# V2_0.net
KiCad netlist of a schematic drawn in Altium Designer
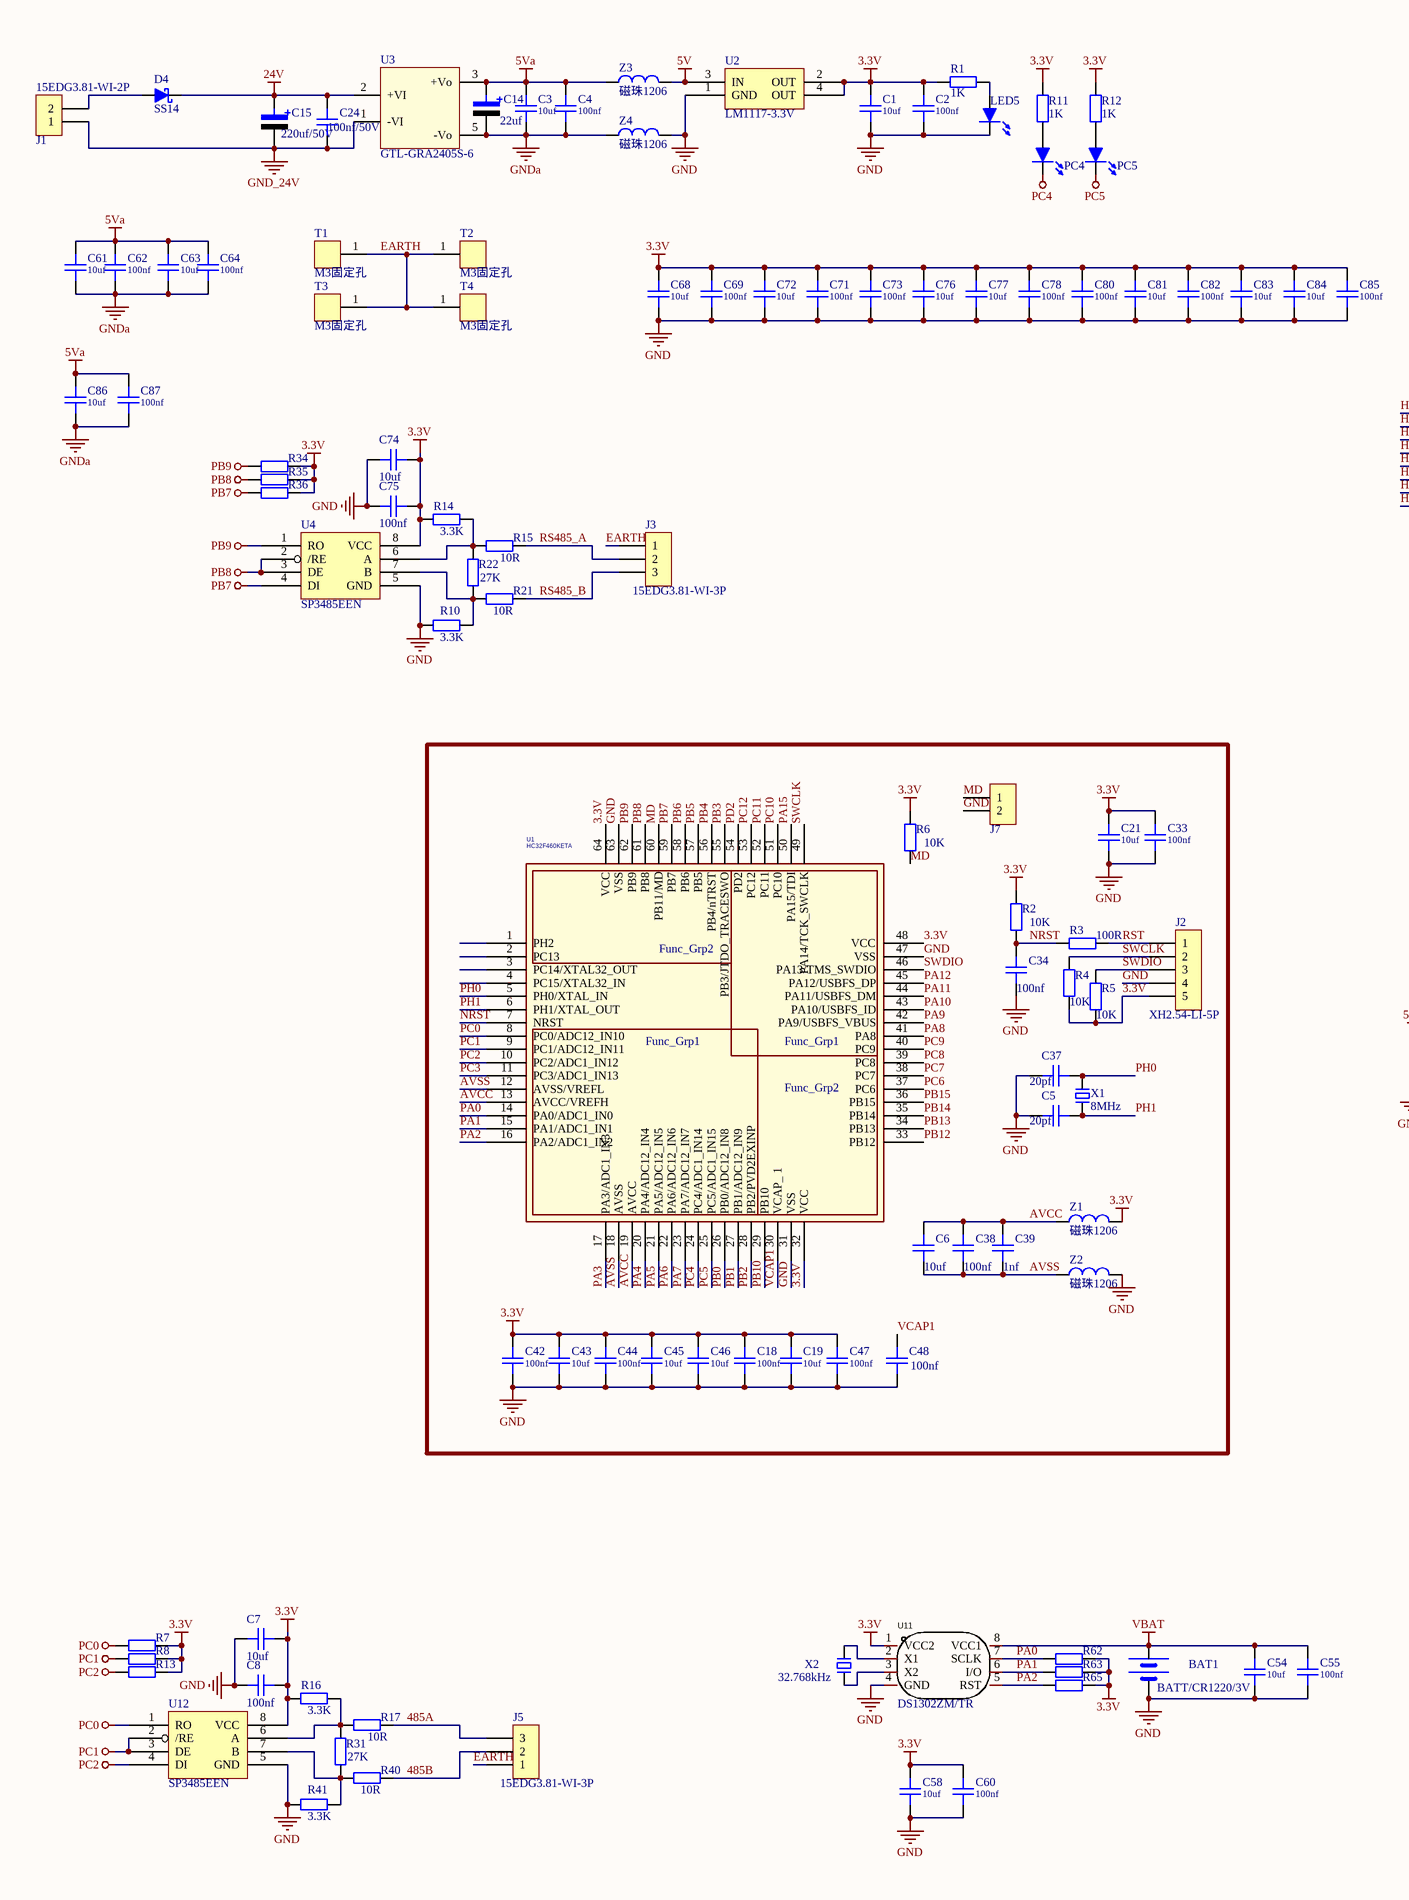
[diagram p0: 微断从V2.0.SchDoc, left]
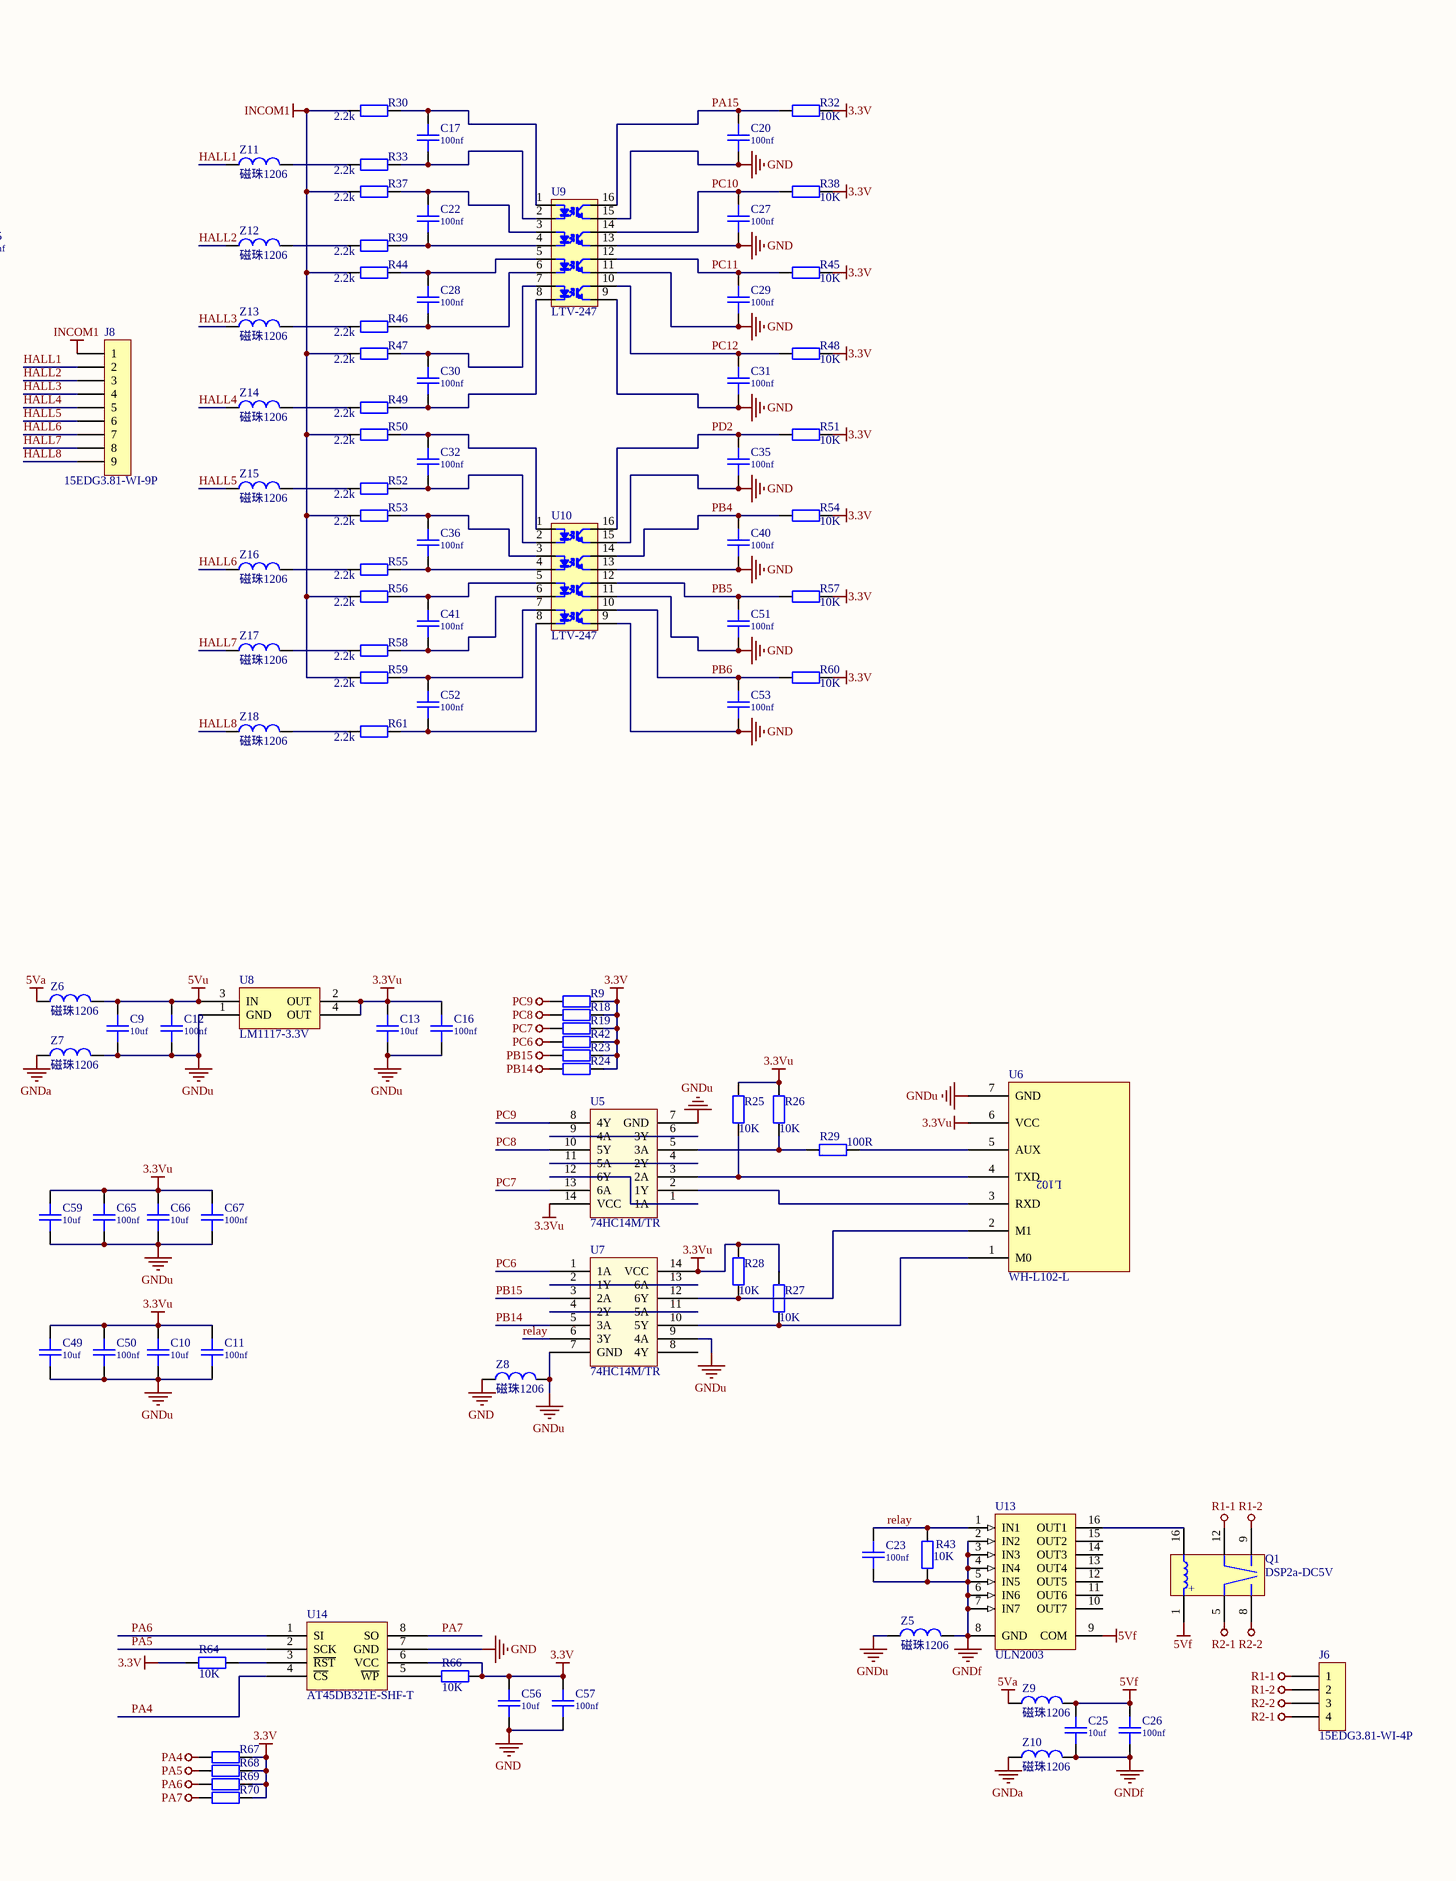
[diagram p1: 微断从V2.0.SchDoc, right]

(export (version "E")
  (design (tool "Eeschema 10.0.6"))
  (components
    (comp (ref "BAT1")
      (value "BATT/CR1220/3V")
      (footprint "CR1220_A")
      (description "CR1220/3V电池及座")
      (libsource (lib "HZConnector") (part "BAT"))
    )
    (comp (ref "C1")
      (value "10uf")
      (footprint "0805-C")
      (description "贴片瓷片电容")
      (fields (field (name "PUBLISHER") "Altium Limited"))
      (libsource (lib "jay_schlib") (part "Cap-S"))
    )
    (comp (ref "C2")
      (value "100nf")
      (footprint "0603-C")
      (description "贴片瓷片电容")
      (fields (field (name "PUBLISHER") "Altium Limited"))
      (libsource (lib "jay_schlib") (part "Cap-S"))
    )
    (comp (ref "C3")
      (value "10uf")
      (footprint "0805-C")
      (description "贴片瓷片电容")
      (fields (field (name "PUBLISHER") "Altium Limited"))
      (libsource (lib "jay_schlib") (part "Cap-S"))
    )
    (comp (ref "C4")
      (value "100nf")
      (footprint "0603-C")
      (description "贴片瓷片电容")
      (fields (field (name "PUBLISHER") "Altium Limited"))
      (libsource (lib "jay_schlib") (part "Cap-S"))
    )
    (comp (ref "C5")
      (value "20pf")
      (footprint "0603-C")
      (description "贴片瓷片电容")
      (fields (field (name "PUBLISHER") "Altium Limited"))
      (libsource (lib "jay_schlib") (part "Cap-S"))
    )
    (comp (ref "C6")
      (value "10uf")
      (footprint "0805-C")
      (description "贴片瓷片电容")
      (fields (field (name "PUBLISHER") "Altium Limited"))
      (libsource (lib "jay_schlib") (part "Cap-S"))
    )
    (comp (ref "C7")
      (value "10uf")
      (footprint "0805-C")
      (description "贴片瓷片电容")
      (fields (field (name "PUBLISHER") "Altium Limited"))
      (libsource (lib "jay_schlib") (part "Cap-S"))
    )
    (comp (ref "C8")
      (value "100nf")
      (footprint "0603-C")
      (description "贴片瓷片电容")
      (fields (field (name "PUBLISHER") "Altium Limited"))
      (libsource (lib "jay_schlib") (part "Cap-S"))
    )
    (comp (ref "C9")
      (value "10uf")
      (footprint "0805-C")
      (description "贴片瓷片电容")
      (fields (field (name "PUBLISHER") "Altium Limited"))
      (libsource (lib "jay_schlib") (part "Cap-S"))
    )
    (comp (ref "C10")
      (value "10uf")
      (footprint "0805-C")
      (description "贴片瓷片电容")
      (fields (field (name "PUBLISHER") "Altium Limited"))
      (libsource (lib "jay_schlib") (part "Cap-S"))
    )
    (comp (ref "C11")
      (value "100nf")
      (footprint "0603-C")
      (description "贴片瓷片电容")
      (fields (field (name "PUBLISHER") "Altium Limited"))
      (libsource (lib "jay_schlib") (part "Cap-S"))
    )
    (comp (ref "C12")
      (value "100nf")
      (footprint "0603-C")
      (description "贴片瓷片电容")
      (fields (field (name "PUBLISHER") "Altium Limited"))
      (libsource (lib "jay_schlib") (part "Cap-S"))
    )
    (comp (ref "C13")
      (value "10uf")
      (footprint "0805-C")
      (description "贴片瓷片电容")
      (fields (field (name "PUBLISHER") "Altium Limited"))
      (libsource (lib "jay_schlib") (part "Cap-S"))
    )
    (comp (ref "C14")
      (value "22uf")
      (footprint "CD B(3528)")
      (description "插件电解电容")
      (fields (field (name "PUBLISHER") "Altium Limited"))
      (libsource (lib "jay_schlib") (part "Cap-Pol-ER"))
    )
    (comp (ref "C15")
      (value "220uf/50V")
      (footprint "CAP 3.5*8*11.5 - BK")
      (description "插件电解电容")
      (fields (field (name "PUBLISHER") "Altium Limited"))
      (libsource (lib "jay_schlib") (part "Cap-Pol-ER"))
    )
    (comp (ref "C16")
      (value "100nf")
      (footprint "0603-C")
      (description "贴片瓷片电容")
      (fields (field (name "PUBLISHER") "Altium Limited"))
      (libsource (lib "jay_schlib") (part "Cap-S"))
    )
    (comp (ref "C17")
      (value "100nf")
      (footprint "0603-C")
      (description "贴片瓷片电容")
      (fields (field (name "PUBLISHER") "Altium Limited"))
      (libsource (lib "jay_schlib") (part "Cap-S"))
    )
    (comp (ref "C18")
      (value "100nf")
      (footprint "0603-C")
      (description "贴片瓷片电容")
      (fields (field (name "PUBLISHER") "Altium Limited"))
      (libsource (lib "jay_schlib") (part "Cap-S"))
    )
    (comp (ref "C19")
      (value "10uf")
      (footprint "0805-C")
      (description "贴片瓷片电容")
      (fields (field (name "PUBLISHER") "Altium Limited"))
      (libsource (lib "jay_schlib") (part "Cap-S"))
    )
    (comp (ref "C20")
      (value "100nf")
      (footprint "0603-C")
      (description "贴片瓷片电容")
      (fields (field (name "PUBLISHER") "Altium Limited"))
      (libsource (lib "jay_schlib") (part "Cap-S"))
    )
    (comp (ref "C21")
      (value "10uf")
      (footprint "0805-C")
      (description "贴片瓷片电容")
      (fields (field (name "PUBLISHER") "Altium Limited"))
      (libsource (lib "jay_schlib") (part "Cap-S"))
    )
    (comp (ref "C22")
      (value "100nf")
      (footprint "0603-C")
      (description "贴片瓷片电容")
      (fields (field (name "PUBLISHER") "Altium Limited"))
      (libsource (lib "jay_schlib") (part "Cap-S"))
    )
    (comp (ref "C23")
      (value "100nf")
      (footprint "0603-C")
      (description "贴片瓷片电容")
      (fields (field (name "PUBLISHER") "Altium Limited"))
      (libsource (lib "jay_schlib") (part "Cap-S"))
    )
    (comp (ref "C24")
      (value "100nf/50V")
      (footprint "0603-C")
      (description "贴片瓷片电容")
      (fields (field (name "PUBLISHER") "Altium Limited"))
      (libsource (lib "jay_schlib") (part "Cap-S"))
    )
    (comp (ref "C25")
      (value "10uf")
      (footprint "0805-C")
      (description "贴片瓷片电容")
      (fields (field (name "PUBLISHER") "Altium Limited"))
      (libsource (lib "jay_schlib") (part "Cap-S"))
    )
    (comp (ref "C26")
      (value "100nf")
      (footprint "0603-C")
      (description "贴片瓷片电容")
      (fields (field (name "PUBLISHER") "Altium Limited"))
      (libsource (lib "jay_schlib") (part "Cap-S"))
    )
    (comp (ref "C27")
      (value "100nf")
      (footprint "0603-C")
      (description "贴片瓷片电容")
      (fields (field (name "PUBLISHER") "Altium Limited"))
      (libsource (lib "jay_schlib") (part "Cap-S"))
    )
    (comp (ref "C28")
      (value "100nf")
      (footprint "0603-C")
      (description "贴片瓷片电容")
      (fields (field (name "PUBLISHER") "Altium Limited"))
      (libsource (lib "jay_schlib") (part "Cap-S"))
    )
    (comp (ref "C29")
      (value "100nf")
      (footprint "0603-C")
      (description "贴片瓷片电容")
      (fields (field (name "PUBLISHER") "Altium Limited"))
      (libsource (lib "jay_schlib") (part "Cap-S"))
    )
    (comp (ref "C30")
      (value "100nf")
      (footprint "0603-C")
      (description "贴片瓷片电容")
      (fields (field (name "PUBLISHER") "Altium Limited"))
      (libsource (lib "jay_schlib") (part "Cap-S"))
    )
    (comp (ref "C31")
      (value "100nf")
      (footprint "0603-C")
      (description "贴片瓷片电容")
      (fields (field (name "PUBLISHER") "Altium Limited"))
      (libsource (lib "jay_schlib") (part "Cap-S"))
    )
    (comp (ref "C32")
      (value "100nf")
      (footprint "0603-C")
      (description "贴片瓷片电容")
      (fields (field (name "PUBLISHER") "Altium Limited"))
      (libsource (lib "jay_schlib") (part "Cap-S"))
    )
    (comp (ref "C33")
      (value "100nf")
      (footprint "0603-C")
      (description "贴片瓷片电容")
      (fields (field (name "PUBLISHER") "Altium Limited"))
      (libsource (lib "jay_schlib") (part "Cap-S"))
    )
    (comp (ref "C34")
      (value "100nf")
      (footprint "0603-C")
      (description "贴片瓷片电容")
      (fields (field (name "PUBLISHER") "Altium Limited"))
      (libsource (lib "jay_schlib") (part "Cap-S"))
    )
    (comp (ref "C35")
      (value "100nf")
      (footprint "0603-C")
      (description "贴片瓷片电容")
      (fields (field (name "PUBLISHER") "Altium Limited"))
      (libsource (lib "jay_schlib") (part "Cap-S"))
    )
    (comp (ref "C36")
      (value "100nf")
      (footprint "0603-C")
      (description "贴片瓷片电容")
      (fields (field (name "PUBLISHER") "Altium Limited"))
      (libsource (lib "jay_schlib") (part "Cap-S"))
    )
    (comp (ref "C37")
      (value "20pf")
      (footprint "0603-C")
      (description "贴片瓷片电容")
      (fields (field (name "PUBLISHER") "Altium Limited"))
      (libsource (lib "jay_schlib") (part "Cap-S"))
    )
    (comp (ref "C38")
      (value "100nf")
      (footprint "0603-C")
      (description "贴片瓷片电容")
      (fields (field (name "PUBLISHER") "Altium Limited"))
      (libsource (lib "jay_schlib") (part "Cap-S"))
    )
    (comp (ref "C39")
      (value "1nf")
      (footprint "0603-C")
      (description "贴片瓷片电容")
      (fields (field (name "PUBLISHER") "Altium Limited"))
      (libsource (lib "jay_schlib") (part "Cap-S"))
    )
    (comp (ref "C40")
      (value "100nf")
      (footprint "0603-C")
      (description "贴片瓷片电容")
      (fields (field (name "PUBLISHER") "Altium Limited"))
      (libsource (lib "jay_schlib") (part "Cap-S"))
    )
    (comp (ref "C41")
      (value "100nf")
      (footprint "0603-C")
      (description "贴片瓷片电容")
      (fields (field (name "PUBLISHER") "Altium Limited"))
      (libsource (lib "jay_schlib") (part "Cap-S"))
    )
    (comp (ref "C42")
      (value "100nf")
      (footprint "0603-C")
      (description "贴片瓷片电容")
      (fields (field (name "PUBLISHER") "Altium Limited"))
      (libsource (lib "jay_schlib") (part "Cap-S"))
    )
    (comp (ref "C43")
      (value "10uf")
      (footprint "0805-C")
      (description "贴片瓷片电容")
      (fields (field (name "PUBLISHER") "Altium Limited"))
      (libsource (lib "jay_schlib") (part "Cap-S"))
    )
    (comp (ref "C44")
      (value "100nf")
      (footprint "0603-C")
      (description "贴片瓷片电容")
      (fields (field (name "PUBLISHER") "Altium Limited"))
      (libsource (lib "jay_schlib") (part "Cap-S"))
    )
    (comp (ref "C45")
      (value "10uf")
      (footprint "0805-C")
      (description "贴片瓷片电容")
      (fields (field (name "PUBLISHER") "Altium Limited"))
      (libsource (lib "jay_schlib") (part "Cap-S"))
    )
    (comp (ref "C46")
      (value "10uf")
      (footprint "0805-C")
      (description "贴片瓷片电容")
      (fields (field (name "PUBLISHER") "Altium Limited"))
      (libsource (lib "jay_schlib") (part "Cap-S"))
    )
    (comp (ref "C47")
      (value "100nf")
      (footprint "0603-C")
      (description "贴片瓷片电容")
      (fields (field (name "PUBLISHER") "Altium Limited"))
      (libsource (lib "jay_schlib") (part "Cap-S"))
    )
    (comp (ref "C48")
      (value "100nf")
      (footprint "0603-C")
      (description "贴片瓷片电容")
      (fields (field (name "PUBLISHER") "Altium Limited"))
      (libsource (lib "jay_schlib") (part "Cap-S"))
    )
    (comp (ref "C49")
      (value "10uf")
      (footprint "0805-C")
      (description "贴片瓷片电容")
      (fields (field (name "PUBLISHER") "Altium Limited"))
      (libsource (lib "jay_schlib") (part "Cap-S"))
    )
    (comp (ref "C50")
      (value "100nf")
      (footprint "0603-C")
      (description "贴片瓷片电容")
      (fields (field (name "PUBLISHER") "Altium Limited"))
      (libsource (lib "jay_schlib") (part "Cap-S"))
    )
    (comp (ref "C51")
      (value "100nf")
      (footprint "0603-C")
      (description "贴片瓷片电容")
      (fields (field (name "PUBLISHER") "Altium Limited"))
      (libsource (lib "jay_schlib") (part "Cap-S"))
    )
    (comp (ref "C52")
      (value "100nf")
      (footprint "0603-C")
      (description "贴片瓷片电容")
      (fields (field (name "PUBLISHER") "Altium Limited"))
      (libsource (lib "jay_schlib") (part "Cap-S"))
    )
    (comp (ref "C53")
      (value "100nf")
      (footprint "0603-C")
      (description "贴片瓷片电容")
      (fields (field (name "PUBLISHER") "Altium Limited"))
      (libsource (lib "jay_schlib") (part "Cap-S"))
    )
    (comp (ref "C54")
      (value "10uf")
      (footprint "0805-C")
      (description "贴片瓷片电容")
      (fields (field (name "PUBLISHER") "Altium Limited"))
      (libsource (lib "jay_schlib") (part "Cap-S"))
    )
    (comp (ref "C55")
      (value "100nf")
      (footprint "0603-C")
      (description "贴片瓷片电容")
      (fields (field (name "PUBLISHER") "Altium Limited"))
      (libsource (lib "jay_schlib") (part "Cap-S"))
    )
    (comp (ref "C56")
      (value "10uf")
      (footprint "0805-C")
      (description "贴片瓷片电容")
      (fields (field (name "PUBLISHER") "Altium Limited"))
      (libsource (lib "jay_schlib") (part "Cap-S"))
    )
    (comp (ref "C57")
      (value "100nf")
      (footprint "0603-C")
      (description "贴片瓷片电容")
      (fields (field (name "PUBLISHER") "Altium Limited"))
      (libsource (lib "jay_schlib") (part "Cap-S"))
    )
    (comp (ref "C58")
      (value "10uf")
      (footprint "0805-C")
      (description "贴片瓷片电容")
      (fields (field (name "PUBLISHER") "Altium Limited"))
      (libsource (lib "jay_schlib") (part "Cap-S"))
    )
    (comp (ref "C59")
      (value "10uf")
      (footprint "0805-C")
      (description "贴片瓷片电容")
      (fields (field (name "PUBLISHER") "Altium Limited"))
      (libsource (lib "jay_schlib") (part "Cap-S"))
    )
    (comp (ref "C60")
      (value "100nf")
      (footprint "0603-C")
      (description "贴片瓷片电容")
      (fields (field (name "PUBLISHER") "Altium Limited"))
      (libsource (lib "jay_schlib") (part "Cap-S"))
    )
    (comp (ref "C61")
      (value "10uf")
      (footprint "0805-C")
      (description "贴片瓷片电容")
      (fields (field (name "PUBLISHER") "Altium Limited"))
      (libsource (lib "jay_schlib") (part "Cap-S"))
    )
    (comp (ref "C62")
      (value "100nf")
      (footprint "0603-C")
      (description "贴片瓷片电容")
      (fields (field (name "PUBLISHER") "Altium Limited"))
      (libsource (lib "jay_schlib") (part "Cap-S"))
    )
    (comp (ref "C63")
      (value "10uf")
      (footprint "0805-C")
      (description "贴片瓷片电容")
      (fields (field (name "PUBLISHER") "Altium Limited"))
      (libsource (lib "jay_schlib") (part "Cap-S"))
    )
    (comp (ref "C64")
      (value "100nf")
      (footprint "0603-C")
      (description "贴片瓷片电容")
      (fields (field (name "PUBLISHER") "Altium Limited"))
      (libsource (lib "jay_schlib") (part "Cap-S"))
    )
    (comp (ref "C65")
      (value "100nf")
      (footprint "0603-C")
      (description "贴片瓷片电容")
      (fields (field (name "PUBLISHER") "Altium Limited"))
      (libsource (lib "jay_schlib") (part "Cap-S"))
    )
    (comp (ref "C66")
      (value "10uf")
      (footprint "0805-C")
      (description "贴片瓷片电容")
      (fields (field (name "PUBLISHER") "Altium Limited"))
      (libsource (lib "jay_schlib") (part "Cap-S"))
    )
    (comp (ref "C67")
      (value "100nf")
      (footprint "0603-C")
      (description "贴片瓷片电容")
      (fields (field (name "PUBLISHER") "Altium Limited"))
      (libsource (lib "jay_schlib") (part "Cap-S"))
    )
    (comp (ref "C68")
      (value "10uf")
      (footprint "0805-C")
      (description "贴片瓷片电容")
      (fields (field (name "PUBLISHER") "Altium Limited"))
      (libsource (lib "jay_schlib") (part "Cap-S"))
    )
    (comp (ref "C69")
      (value "100nf")
      (footprint "0603-C")
      (description "贴片瓷片电容")
      (fields (field (name "PUBLISHER") "Altium Limited"))
      (libsource (lib "jay_schlib") (part "Cap-S"))
    )
    (comp (ref "C71")
      (value "100nf")
      (footprint "0603-C")
      (description "贴片瓷片电容")
      (fields (field (name "PUBLISHER") "Altium Limited"))
      (libsource (lib "jay_schlib") (part "Cap-S"))
    )
    (comp (ref "C72")
      (value "10uf")
      (footprint "0805-C")
      (description "贴片瓷片电容")
      (fields (field (name "PUBLISHER") "Altium Limited"))
      (libsource (lib "jay_schlib") (part "Cap-S"))
    )
    (comp (ref "C73")
      (value "100nf")
      (footprint "0603-C")
      (description "贴片瓷片电容")
      (fields (field (name "PUBLISHER") "Altium Limited"))
      (libsource (lib "jay_schlib") (part "Cap-S"))
    )
    (comp (ref "C74")
      (value "10uf")
      (footprint "0805-C")
      (description "贴片瓷片电容")
      (fields (field (name "PUBLISHER") "Altium Limited"))
      (libsource (lib "jay_schlib") (part "Cap-S"))
    )
    (comp (ref "C75")
      (value "100nf")
      (footprint "0603-C")
      (description "贴片瓷片电容")
      (fields (field (name "PUBLISHER") "Altium Limited"))
      (libsource (lib "jay_schlib") (part "Cap-S"))
    )
    (comp (ref "C76")
      (value "10uf")
      (footprint "0805-C")
      (description "贴片瓷片电容")
      (fields (field (name "PUBLISHER") "Altium Limited"))
      (libsource (lib "jay_schlib") (part "Cap-S"))
    )
    (comp (ref "C77")
      (value "10uf")
      (footprint "0805-C")
      (description "贴片瓷片电容")
      (fields (field (name "PUBLISHER") "Altium Limited"))
      (libsource (lib "jay_schlib") (part "Cap-S"))
    )
    (comp (ref "C78")
      (value "100nf")
      (footprint "0603-C")
      (description "贴片瓷片电容")
      (fields (field (name "PUBLISHER") "Altium Limited"))
      (libsource (lib "jay_schlib") (part "Cap-S"))
    )
    (comp (ref "C80")
      (value "100nf")
      (footprint "0603-C")
      (description "贴片瓷片电容")
      (fields (field (name "PUBLISHER") "Altium Limited"))
      (libsource (lib "jay_schlib") (part "Cap-S"))
    )
    (comp (ref "C81")
      (value "10uf")
      (footprint "0805-C")
      (description "贴片瓷片电容")
      (fields (field (name "PUBLISHER") "Altium Limited"))
      (libsource (lib "jay_schlib") (part "Cap-S"))
    )
    (comp (ref "C82")
      (value "100nf")
      (footprint "0603-C")
      (description "贴片瓷片电容")
      (fields (field (name "PUBLISHER") "Altium Limited"))
      (libsource (lib "jay_schlib") (part "Cap-S"))
    )
    (comp (ref "C83")
      (value "10uf")
      (footprint "0805-C")
      (description "贴片瓷片电容")
      (fields (field (name "PUBLISHER") "Altium Limited"))
      (libsource (lib "jay_schlib") (part "Cap-S"))
    )
    (comp (ref "C84")
      (value "10uf")
      (footprint "0805-C")
      (description "贴片瓷片电容")
      (fields (field (name "PUBLISHER") "Altium Limited"))
      (libsource (lib "jay_schlib") (part "Cap-S"))
    )
    (comp (ref "C85")
      (value "100nf")
      (footprint "0603-C")
      (description "贴片瓷片电容")
      (fields (field (name "PUBLISHER") "Altium Limited"))
      (libsource (lib "jay_schlib") (part "Cap-S"))
    )
    (comp (ref "C86")
      (value "10uf")
      (footprint "0805-C")
      (description "贴片瓷片电容")
      (fields (field (name "PUBLISHER") "Altium Limited"))
      (libsource (lib "jay_schlib") (part "Cap-S"))
    )
    (comp (ref "C87")
      (value "100nf")
      (footprint "0603-C")
      (description "贴片瓷片电容")
      (fields (field (name "PUBLISHER") "Altium Limited"))
      (libsource (lib "jay_schlib") (part "Cap-S"))
    )
    (comp (ref "D4")
      (value "SS14")
      (footprint "SMA/DO-214AC")
      (description "肖特基二极管")
      (fields (field (name "PUBLISHER") "Altium Limited"))
      (libsource (lib "jay_schlib") (part "Diode2"))
    )
    (comp (ref "J1")
      (value "15EDG3.81-WI-2P")
      (footprint "15EDG3.81-WI-2P")
      (description "接插件")
      (fields (field (name "PUBLISHER") "Altium Limited"))
      (libsource (lib "jay_schlib") (part "Header 2"))
    )
    (comp (ref "J2")
      (value "XH2.54-LI-5P")
      (footprint "XH2.54-LI-5P")
      (description "接插件")
      (fields (field (name "PUBLISHER") "Altium Limited"))
      (libsource (lib "jay_schlib") (part "Header 5"))
    )
    (comp (ref "J3")
      (value "15EDG3.81-WI-3P")
      (footprint "15EDG3.81-WI-3P")
      (description "接插件")
      (fields (field (name "PUBLISHER") "Altium Limited"))
      (libsource (lib "jay_schlib") (part "Header 3"))
    )
    (comp (ref "J5")
      (value "15EDG3.81-WI-3P")
      (footprint "15EDG3.81-WI-3P")
      (description "接插件")
      (fields (field (name "PUBLISHER") "Altium Limited"))
      (libsource (lib "") (part "Header 3_1"))
    )
    (comp (ref "J6")
      (value "15EDG3.81-WI-4P")
      (footprint "15EDG3.81-WI-4P")
      (description "接插件")
      (fields (field (name "PUBLISHER") "Altium Limited"))
      (libsource (lib "jay_schlib") (part "Header 4"))
    )
    (comp (ref "J7")
      (value "排针1*2P")
      (footprint "HDR2X1_A")
      (description "接插件")
      (fields (field (name "PUBLISHER") "Altium Limited"))
      (libsource (lib "") (part "Header 2_1"))
    )
    (comp (ref "J8")
      (value "15EDG3.81-WI-9P")
      (footprint "15EDG3.81-WI-9P")
      (description "Header, 9-Pin")
      (fields (field (name "PUBLISHER") "Altium Limited"))
      (libsource (lib "jay_schlib") (part "Header 9"))
    )
    (comp (ref "LED5")
      (value "LED0603,黄绿")
      (footprint "0603-LED-G")
      (description "发光二极管")
      (fields (field (name "PUBLISHER") "Altium Limited"))
      (libsource (lib "jay_schlib") (part "LED"))
    )
    (comp (ref "PC4")
      (value "LED0603,黄绿")
      (footprint "0603-LED-G")
      (description "发光二极管")
      (fields (field (name "PUBLISHER") "Altium Limited"))
      (libsource (lib "jay_schlib") (part "LED"))
    )
    (comp (ref "PC5")
      (value "LED0603,黄绿")
      (footprint "0603-LED-G")
      (description "发光二极管")
      (fields (field (name "PUBLISHER") "Altium Limited"))
      (libsource (lib "jay_schlib") (part "LED"))
    )
    (comp (ref "Q1")
      (value "DSP2a-DC5V")
      (footprint "DSP2a-DC5V")
      (description "松下继电器")
      (libsource (lib "jay_schlib") (part "DSP2a-DC5V"))
    )
    (comp (ref "R1")
      (value "1K")
      (footprint "0603-R")
      (description "贴片电阻")
      (fields (field (name "PUBLISHER") "Altium Limited"))
      (libsource (lib "jay_schlib") (part "Res1"))
    )
    (comp (ref "R2")
      (value "10K")
      (footprint "0603-R")
      (description "贴片电阻")
      (fields (field (name "PUBLISHER") "Altium Limited"))
      (libsource (lib "") (part "Res1_2"))
    )
    (comp (ref "R3")
      (value "100R")
      (footprint "0603-R")
      (description "贴片电阻")
      (fields (field (name "PUBLISHER") "Altium Limited"))
      (libsource (lib "jay_schlib") (part "Res1"))
    )
    (comp (ref "R4")
      (value "10K")
      (footprint "0603-R")
      (description "贴片电阻")
      (fields (field (name "PUBLISHER") "Altium Limited"))
      (libsource (lib "") (part "Res1_2"))
    )
    (comp (ref "R5")
      (value "10K")
      (footprint "0603-R")
      (description "贴片电阻")
      (fields (field (name "PUBLISHER") "Altium Limited"))
      (libsource (lib "") (part "Res1_2"))
    )
    (comp (ref "R6")
      (value "10K")
      (footprint "0603-R")
      (description "贴片电阻")
      (fields (field (name "PUBLISHER") "Altium Limited"))
      (libsource (lib "") (part "Res1_2"))
    )
    (comp (ref "R7")
      (value "10K")
      (footprint "0603-R")
      (description "贴片电阻")
      (fields (field (name "PUBLISHER") "Altium Limited"))
      (libsource (lib "") (part "Res1_1"))
    )
    (comp (ref "R8")
      (value "10K")
      (footprint "0603-R")
      (description "贴片电阻")
      (fields (field (name "PUBLISHER") "Altium Limited"))
      (libsource (lib "") (part "Res1_1"))
    )
    (comp (ref "R9")
      (value "10K")
      (footprint "0603-R")
      (description "贴片电阻")
      (fields (field (name "PUBLISHER") "Altium Limited"))
      (libsource (lib "jay_schlib") (part "Res1"))
    )
    (comp (ref "R10")
      (value "3.3K")
      (footprint "0603-R")
      (description "Resistor")
      (fields (field (name "PUBLISHER") "Altium Limited"))
      (libsource (lib "*") (part "Res2"))
    )
    (comp (ref "R11")
      (value "1K")
      (footprint "0603-R")
      (description "贴片电阻")
      (fields (field (name "PUBLISHER") "Altium Limited"))
      (libsource (lib "") (part "Res1_2"))
    )
    (comp (ref "R12")
      (value "1K")
      (footprint "0603-R")
      (description "贴片电阻")
      (fields (field (name "PUBLISHER") "Altium Limited"))
      (libsource (lib "") (part "Res1_2"))
    )
    (comp (ref "R13")
      (value "10K")
      (footprint "0603-R")
      (description "贴片电阻")
      (fields (field (name "PUBLISHER") "Altium Limited"))
      (libsource (lib "") (part "Res1_1"))
    )
    (comp (ref "R14")
      (value "3.3K")
      (footprint "0603-R")
      (description "Resistor")
      (fields (field (name "PUBLISHER") "Altium Limited"))
      (libsource (lib "") (part "Res2_2"))
    )
    (comp (ref "R15")
      (value "10R")
      (footprint "0603-R")
      (description "Resistor")
      (fields (field (name "PUBLISHER") "Altium Limited"))
      (libsource (lib "*") (part "Res2"))
    )
    (comp (ref "R16")
      (value "3.3K")
      (footprint "0603-R")
      (description "Resistor")
      (fields (field (name "PUBLISHER") "Altium Limited"))
      (libsource (lib "") (part "Res2_2"))
    )
    (comp (ref "R17")
      (value "10R")
      (footprint "0603-R")
      (description "Resistor")
      (fields (field (name "PUBLISHER") "Altium Limited"))
      (libsource (lib "*") (part "Res2"))
    )
    (comp (ref "R18")
      (value "10K")
      (footprint "0603-R")
      (description "贴片电阻")
      (fields (field (name "PUBLISHER") "Altium Limited"))
      (libsource (lib "jay_schlib") (part "Res1"))
    )
    (comp (ref "R19")
      (value "10K")
      (footprint "0603-R")
      (description "贴片电阻")
      (fields (field (name "PUBLISHER") "Altium Limited"))
      (libsource (lib "jay_schlib") (part "Res1"))
    )
    (comp (ref "R21")
      (value "10R")
      (footprint "0603-R")
      (description "Resistor")
      (fields (field (name "PUBLISHER") "Altium Limited"))
      (libsource (lib "*") (part "Res2"))
    )
    (comp (ref "R22")
      (value "27K")
      (footprint "0603-R")
      (description "Resistor")
      (fields (field (name "PUBLISHER") "Altium Limited"))
      (libsource (lib "") (part "Res2_1"))
    )
    (comp (ref "R23")
      (value "10K")
      (footprint "0603-R")
      (description "贴片电阻")
      (fields (field (name "PUBLISHER") "Altium Limited"))
      (libsource (lib "jay_schlib") (part "Res1"))
    )
    (comp (ref "R24")
      (value "10K")
      (footprint "0603-R")
      (description "贴片电阻")
      (fields (field (name "PUBLISHER") "Altium Limited"))
      (libsource (lib "jay_schlib") (part "Res1"))
    )
    (comp (ref "R25")
      (value "10K")
      (footprint "0603-R")
      (description "贴片电阻")
      (fields (field (name "PUBLISHER") "Altium Limited"))
      (libsource (lib "") (part "Res1_2"))
    )
    (comp (ref "R26")
      (value "10K")
      (footprint "0603-R")
      (description "贴片电阻")
      (fields (field (name "PUBLISHER") "Altium Limited"))
      (libsource (lib "") (part "Res1_2"))
    )
    (comp (ref "R27")
      (value "10K")
      (footprint "0603-R")
      (description "贴片电阻")
      (fields (field (name "PUBLISHER") "Altium Limited"))
      (libsource (lib "") (part "Res1_2"))
    )
    (comp (ref "R28")
      (value "10K")
      (footprint "0603-R")
      (description "贴片电阻")
      (fields (field (name "PUBLISHER") "Altium Limited"))
      (libsource (lib "") (part "Res1_2"))
    )
    (comp (ref "R29")
      (value "100R")
      (footprint "0603-R")
      (description "贴片电阻")
      (fields (field (name "PUBLISHER") "Altium Limited"))
      (libsource (lib "jay_schlib") (part "Res1"))
    )
    (comp (ref "R30")
      (value "2.2k")
      (footprint "0603-R")
      (description "贴片电阻")
      (fields (field (name "PUBLISHER") "Altium Limited"))
      (libsource (lib "jay_schlib") (part "Res1"))
    )
    (comp (ref "R31")
      (value "27K")
      (footprint "0603-R")
      (description "Resistor")
      (fields (field (name "PUBLISHER") "Altium Limited"))
      (libsource (lib "") (part "Res2_1"))
    )
    (comp (ref "R32")
      (value "10K")
      (footprint "0603-R")
      (description "贴片电阻")
      (fields (field (name "PUBLISHER") "Altium Limited"))
      (libsource (lib "jay_schlib") (part "Res1"))
    )
    (comp (ref "R33")
      (value "2.2k")
      (footprint "0603-R")
      (description "贴片电阻")
      (fields (field (name "PUBLISHER") "Altium Limited"))
      (libsource (lib "jay_schlib") (part "Res1"))
    )
    (comp (ref "R34")
      (value "10K")
      (footprint "0603-R")
      (description "贴片电阻")
      (fields (field (name "PUBLISHER") "Altium Limited"))
      (libsource (lib "") (part "Res1_1"))
    )
    (comp (ref "R35")
      (value "10K")
      (footprint "0603-R")
      (description "贴片电阻")
      (fields (field (name "PUBLISHER") "Altium Limited"))
      (libsource (lib "") (part "Res1_1"))
    )
    (comp (ref "R36")
      (value "10K")
      (footprint "0603-R")
      (description "贴片电阻")
      (fields (field (name "PUBLISHER") "Altium Limited"))
      (libsource (lib "") (part "Res1_1"))
    )
    (comp (ref "R37")
      (value "2.2k")
      (footprint "0603-R")
      (description "贴片电阻")
      (fields (field (name "PUBLISHER") "Altium Limited"))
      (libsource (lib "jay_schlib") (part "Res1"))
    )
    (comp (ref "R38")
      (value "10K")
      (footprint "0603-R")
      (description "贴片电阻")
      (fields (field (name "PUBLISHER") "Altium Limited"))
      (libsource (lib "jay_schlib") (part "Res1"))
    )
    (comp (ref "R39")
      (value "2.2k")
      (footprint "0603-R")
      (description "贴片电阻")
      (fields (field (name "PUBLISHER") "Altium Limited"))
      (libsource (lib "jay_schlib") (part "Res1"))
    )
    (comp (ref "R40")
      (value "10R")
      (footprint "0603-R")
      (description "Resistor")
      (fields (field (name "PUBLISHER") "Altium Limited"))
      (libsource (lib "*") (part "Res2"))
    )
    (comp (ref "R41")
      (value "3.3K")
      (footprint "0603-R")
      (description "Resistor")
      (fields (field (name "PUBLISHER") "Altium Limited"))
      (libsource (lib "*") (part "Res2"))
    )
    (comp (ref "R42")
      (value "10K")
      (footprint "0603-R")
      (description "贴片电阻")
      (fields (field (name "PUBLISHER") "Altium Limited"))
      (libsource (lib "jay_schlib") (part "Res1"))
    )
    (comp (ref "R43")
      (value "10K")
      (footprint "0603-R")
      (description "贴片电阻")
      (fields (field (name "PUBLISHER") "Altium Limited"))
      (libsource (lib "") (part "Res1_1"))
    )
    (comp (ref "R44")
      (value "2.2k")
      (footprint "0603-R")
      (description "贴片电阻")
      (fields (field (name "PUBLISHER") "Altium Limited"))
      (libsource (lib "jay_schlib") (part "Res1"))
    )
    (comp (ref "R45")
      (value "10K")
      (footprint "0603-R")
      (description "贴片电阻")
      (fields (field (name "PUBLISHER") "Altium Limited"))
      (libsource (lib "jay_schlib") (part "Res1"))
    )
    (comp (ref "R46")
      (value "2.2k")
      (footprint "0603-R")
      (description "贴片电阻")
      (fields (field (name "PUBLISHER") "Altium Limited"))
      (libsource (lib "jay_schlib") (part "Res1"))
    )
    (comp (ref "R47")
      (value "2.2k")
      (footprint "0603-R")
      (description "贴片电阻")
      (fields (field (name "PUBLISHER") "Altium Limited"))
      (libsource (lib "jay_schlib") (part "Res1"))
    )
    (comp (ref "R48")
      (value "10K")
      (footprint "0603-R")
      (description "贴片电阻")
      (fields (field (name "PUBLISHER") "Altium Limited"))
      (libsource (lib "jay_schlib") (part "Res1"))
    )
    (comp (ref "R49")
      (value "2.2k")
      (footprint "0603-R")
      (description "贴片电阻")
      (fields (field (name "PUBLISHER") "Altium Limited"))
      (libsource (lib "jay_schlib") (part "Res1"))
    )
    (comp (ref "R50")
      (value "2.2k")
      (footprint "0603-R")
      (description "贴片电阻")
      (fields (field (name "PUBLISHER") "Altium Limited"))
      (libsource (lib "jay_schlib") (part "Res1"))
    )
    (comp (ref "R51")
      (value "10K")
      (footprint "0603-R")
      (description "贴片电阻")
      (fields (field (name "PUBLISHER") "Altium Limited"))
      (libsource (lib "jay_schlib") (part "Res1"))
    )
    (comp (ref "R52")
      (value "2.2k")
      (footprint "0603-R")
      (description "贴片电阻")
      (fields (field (name "PUBLISHER") "Altium Limited"))
      (libsource (lib "jay_schlib") (part "Res1"))
    )
    (comp (ref "R53")
      (value "2.2k")
      (footprint "0603-R")
      (description "贴片电阻")
      (fields (field (name "PUBLISHER") "Altium Limited"))
      (libsource (lib "jay_schlib") (part "Res1"))
    )
    (comp (ref "R54")
      (value "10K")
      (footprint "0603-R")
      (description "贴片电阻")
      (fields (field (name "PUBLISHER") "Altium Limited"))
      (libsource (lib "jay_schlib") (part "Res1"))
    )
    (comp (ref "R55")
      (value "2.2k")
      (footprint "0603-R")
      (description "贴片电阻")
      (fields (field (name "PUBLISHER") "Altium Limited"))
      (libsource (lib "jay_schlib") (part "Res1"))
    )
    (comp (ref "R56")
      (value "2.2k")
      (footprint "0603-R")
      (description "贴片电阻")
      (fields (field (name "PUBLISHER") "Altium Limited"))
      (libsource (lib "jay_schlib") (part "Res1"))
    )
    (comp (ref "R57")
      (value "10K")
      (footprint "0603-R")
      (description "贴片电阻")
      (fields (field (name "PUBLISHER") "Altium Limited"))
      (libsource (lib "jay_schlib") (part "Res1"))
    )
    (comp (ref "R58")
      (value "2.2k")
      (footprint "0603-R")
      (description "贴片电阻")
      (fields (field (name "PUBLISHER") "Altium Limited"))
      (libsource (lib "jay_schlib") (part "Res1"))
    )
    (comp (ref "R59")
      (value "2.2k")
      (footprint "0603-R")
      (description "贴片电阻")
      (fields (field (name "PUBLISHER") "Altium Limited"))
      (libsource (lib "jay_schlib") (part "Res1"))
    )
    (comp (ref "R60")
      (value "10K")
      (footprint "0603-R")
      (description "贴片电阻")
      (fields (field (name "PUBLISHER") "Altium Limited"))
      (libsource (lib "jay_schlib") (part "Res1"))
    )
    (comp (ref "R61")
      (value "2.2k")
      (footprint "0603-R")
      (description "贴片电阻")
      (fields (field (name "PUBLISHER") "Altium Limited"))
      (libsource (lib "jay_schlib") (part "Res1"))
    )
    (comp (ref "R62")
      (value "10K")
      (footprint "0603-R")
      (description "贴片电阻")
      (fields (field (name "PUBLISHER") "Altium Limited"))
      (libsource (lib "jay_schlib") (part "Res1"))
    )
    (comp (ref "R63")
      (value "10K")
      (footprint "0603-R")
      (description "贴片电阻")
      (fields (field (name "PUBLISHER") "Altium Limited"))
      (libsource (lib "jay_schlib") (part "Res1"))
    )
    (comp (ref "R64")
      (value "10K")
      (footprint "0603-R")
      (description "贴片电阻")
      (fields (field (name "PUBLISHER") "Altium Limited"))
      (libsource (lib "jay_schlib") (part "Res1"))
    )
    (comp (ref "R65")
      (value "10K")
      (footprint "0603-R")
      (description "贴片电阻")
      (fields (field (name "PUBLISHER") "Altium Limited"))
      (libsource (lib "jay_schlib") (part "Res1"))
    )
    (comp (ref "R66")
      (value "10K")
      (footprint "0603-R")
      (description "贴片电阻")
      (fields (field (name "PUBLISHER") "Altium Limited"))
      (libsource (lib "jay_schlib") (part "Res1"))
    )
    (comp (ref "R67")
      (value "10K")
      (footprint "0603-R")
      (description "贴片电阻")
      (fields (field (name "PUBLISHER") "Altium Limited"))
      (libsource (lib "") (part "Res1_1"))
    )
    (comp (ref "R68")
      (value "10K")
      (footprint "0603-R")
      (description "贴片电阻")
      (fields (field (name "PUBLISHER") "Altium Limited"))
      (libsource (lib "") (part "Res1_1"))
    )
    (comp (ref "R69")
      (value "10K")
      (footprint "0603-R")
      (description "贴片电阻")
      (fields (field (name "PUBLISHER") "Altium Limited"))
      (libsource (lib "") (part "Res1_1"))
    )
    (comp (ref "R70")
      (value "10K")
      (footprint "0603-R")
      (description "贴片电阻")
      (fields (field (name "PUBLISHER") "Altium Limited"))
      (libsource (lib "") (part "Res1_1"))
    )
    (comp (ref "T1")
      (value "M3固定孔")
      (footprint "M3_N")
      (description "自选封装")
      (libsource (lib "jay_schlib") (part "something_1"))
    )
    (comp (ref "T2")
      (value "M3固定孔")
      (footprint "M3_N")
      (description "自选封装")
      (libsource (lib "") (part "something_1_1"))
    )
    (comp (ref "T3")
      (value "M3固定孔")
      (footprint "M3_N")
      (description "自选封装")
      (libsource (lib "jay_schlib") (part "something_1"))
    )
    (comp (ref "T4")
      (value "M3固定孔")
      (footprint "M3_N")
      (description "自选封装")
      (libsource (lib "") (part "something_1_1"))
    )
    (comp (ref "U1")
      (value "HC32F460KETA")
      (footprint "LQFP-64")
      (libsource (lib "HC32F460") (part "HC32F460KETA"))
    )
    (comp (ref "U2")
      (value "LM1117-3.3V")
      (footprint "SOT223")
      (description "3.3V稳压芯片")
      (libsource (lib "jay_schlib") (part "AMS1117"))
    )
    (comp (ref "U3")
      (value "GTL-GRA2405S-6")
      (footprint "GTL-GRA")
      (description "冠图电子电源模块")
      (libsource (lib "jay_schlib") (part "GTL-GRA"))
    )
    (comp (ref "U4") (value "SP3485EEN") (footprint "SOIC-8") (libsource (lib "*") (part "MAX3082")))
    (comp (ref "U5")
      (value "74HC14M/TR")
      (footprint "SOIC-14")
      (description "反相器")
      (libsource (lib "jay_schlib") (part "74HC14"))
    )
    (comp (ref "U6")
      (value "WH-L102-L")
      (footprint "WH-L102-L_Lib_V1.0")
      (libsource (lib "WH-L102-L_Lib_V1.0") (part "WH-L102-L"))
    )
    (comp (ref "U7")
      (value "74HC14M/TR")
      (footprint "SOIC-14")
      (description "反相器")
      (libsource (lib "") (part "74HC14_1"))
    )
    (comp (ref "U8")
      (value "LM1117-3.3V")
      (footprint "SOT223")
      (description "3.3V稳压芯片")
      (libsource (lib "jay_schlib") (part "AMS1117"))
    )
    (comp (ref "U9")
      (value "LTV-247")
      (footprint "SOIC-16-9.1mm")
      (description "光耦")
      (fields (field (name "PUBLISHER") "Altium Limited"))
      (libsource (lib "jay_schlib") (part "LTV-247"))
    )
    (comp (ref "U10")
      (value "LTV-247")
      (footprint "SOIC-16-9.1mm")
      (description "光耦")
      (fields (field (name "PUBLISHER") "Altium Limited"))
      (libsource (lib "jay_schlib") (part "LTV-247"))
    )
    (comp (ref "U11")
      (value "DS1302ZM/TR")
      (footprint "SOIC-8")
      (fields (field (name "MANUFACTURER") "HGSEMI(华冠)"))
      (libsource (lib "altium-import") (part "root_0_DS1302ZM/TR_"))
    )
    (comp (ref "U12") (value "SP3485EEN") (footprint "SOIC-8") (libsource (lib "*") (part "MAX3082")))
    (comp (ref "U13") (value "ULN2003") (footprint "SOIC-16") (libsource (lib "jay_schlib") (part "ULN2003")))
    (comp (ref "U14")
      (value "AT45DB321E-SHF-T")
      (footprint "SOIC-8-208mil")
      (libsource (lib "*") (part "AT45DB642D"))
    )
    (comp (ref "X1")
      (value "8MHz")
      (footprint "OSC HC-49SMD")
      (description "2脚无源脚晶振")
      (fields (field (name "版权归属") "源创客"))
      (libsource (lib "10.1 - 保险丝-晶振") (part "XTAL-2P"))
    )
    (comp (ref "X2")
      (value "32.768kHz")
      (footprint "OSC HC-49SMD")
      (description "2脚无源脚晶振")
      (fields (field (name "版权归属") "源创客"))
      (libsource (lib "10.1 - 保险丝-晶振") (part "XTAL-2P"))
    )
    (comp (ref "Z1")
      (value "磁珠1206")
      (footprint "1206-R-RP")
      (description "电感")
      (fields (field (name "Comment") "磁珠1206/SCBG321609U600T") (field (name "PUBLISHER") "Altium Limited"))
      (libsource (lib "jay_schlib") (part "Inductor"))
    )
    (comp (ref "Z2")
      (value "磁珠1206")
      (footprint "1206-R-RP")
      (description "电感")
      (fields (field (name "Comment") "磁珠1206/SCBG321609U600T") (field (name "PUBLISHER") "Altium Limited"))
      (libsource (lib "jay_schlib") (part "Inductor"))
    )
    (comp (ref "Z3")
      (value "磁珠1206")
      (footprint "1206-R-RP")
      (description "电感")
      (fields (field (name "Comment") "磁珠1206/SCBG321609U600T") (field (name "PUBLISHER") "Altium Limited"))
      (libsource (lib "jay_schlib") (part "Inductor"))
    )
    (comp (ref "Z4")
      (value "磁珠1206")
      (footprint "1206-R-RP")
      (description "电感")
      (fields (field (name "Comment") "磁珠1206/SCBG321609U600T") (field (name "PUBLISHER") "Altium Limited"))
      (libsource (lib "jay_schlib") (part "Inductor"))
    )
    (comp (ref "Z5")
      (value "磁珠1206")
      (footprint "1206-R-RP")
      (description "电感")
      (fields (field (name "Comment") "磁珠1206/SCBG321609U600T") (field (name "PUBLISHER") "Altium Limited"))
      (libsource (lib "jay_schlib") (part "Inductor"))
    )
    (comp (ref "Z6")
      (value "磁珠1206")
      (footprint "1206-R-RP")
      (description "电感")
      (fields (field (name "Comment") "磁珠1206/SCBG321609U600T") (field (name "PUBLISHER") "Altium Limited"))
      (libsource (lib "jay_schlib") (part "Inductor"))
    )
    (comp (ref "Z7")
      (value "磁珠1206")
      (footprint "1206-R-RP")
      (description "电感")
      (fields (field (name "Comment") "磁珠1206/SCBG321609U600T") (field (name "PUBLISHER") "Altium Limited"))
      (libsource (lib "jay_schlib") (part "Inductor"))
    )
    (comp (ref "Z8")
      (value "磁珠1206")
      (footprint "1206-R-RP")
      (description "电感")
      (fields (field (name "Comment") "磁珠1206/SCBG321609U600T") (field (name "PUBLISHER") "Altium Limited"))
      (libsource (lib "jay_schlib") (part "Inductor"))
    )
    (comp (ref "Z9")
      (value "磁珠1206")
      (footprint "1206-R-RP")
      (description "电感")
      (fields (field (name "Comment") "磁珠1206/SCBG321609U600T") (field (name "PUBLISHER") "Altium Limited"))
      (libsource (lib "jay_schlib") (part "Inductor"))
    )
    (comp (ref "Z10")
      (value "磁珠1206")
      (footprint "1206-R-RP")
      (description "电感")
      (fields (field (name "Comment") "磁珠1206/SCBG321609U600T") (field (name "PUBLISHER") "Altium Limited"))
      (libsource (lib "jay_schlib") (part "Inductor"))
    )
    (comp (ref "Z11")
      (value "磁珠1206")
      (footprint "1206-R-RP")
      (description "电感")
      (fields (field (name "Comment") "磁珠1206/SCBG321609U600T") (field (name "PUBLISHER") "Altium Limited"))
      (libsource (lib "jay_schlib") (part "Inductor"))
    )
    (comp (ref "Z12")
      (value "磁珠1206")
      (footprint "1206-R-RP")
      (description "电感")
      (fields (field (name "Comment") "磁珠1206/SCBG321609U600T") (field (name "PUBLISHER") "Altium Limited"))
      (libsource (lib "jay_schlib") (part "Inductor"))
    )
    (comp (ref "Z13")
      (value "磁珠1206")
      (footprint "1206-R-RP")
      (description "电感")
      (fields (field (name "Comment") "磁珠1206/SCBG321609U600T") (field (name "PUBLISHER") "Altium Limited"))
      (libsource (lib "jay_schlib") (part "Inductor"))
    )
    (comp (ref "Z14")
      (value "磁珠1206")
      (footprint "1206-R-RP")
      (description "电感")
      (fields (field (name "Comment") "磁珠1206/SCBG321609U600T") (field (name "PUBLISHER") "Altium Limited"))
      (libsource (lib "jay_schlib") (part "Inductor"))
    )
    (comp (ref "Z15")
      (value "磁珠1206")
      (footprint "1206-R-RP")
      (description "电感")
      (fields (field (name "Comment") "磁珠1206/SCBG321609U600T") (field (name "PUBLISHER") "Altium Limited"))
      (libsource (lib "jay_schlib") (part "Inductor"))
    )
    (comp (ref "Z16")
      (value "磁珠1206")
      (footprint "1206-R-RP")
      (description "电感")
      (fields (field (name "Comment") "磁珠1206/SCBG321609U600T") (field (name "PUBLISHER") "Altium Limited"))
      (libsource (lib "jay_schlib") (part "Inductor"))
    )
    (comp (ref "Z17")
      (value "磁珠1206")
      (footprint "1206-R-RP")
      (description "电感")
      (fields (field (name "Comment") "磁珠1206/SCBG321609U600T") (field (name "PUBLISHER") "Altium Limited"))
      (libsource (lib "jay_schlib") (part "Inductor"))
    )
    (comp (ref "Z18")
      (value "磁珠1206")
      (footprint "1206-R-RP")
      (description "电感")
      (fields (field (name "Comment") "磁珠1206/SCBG321609U600T") (field (name "PUBLISHER") "Altium Limited"))
      (libsource (lib "jay_schlib") (part "Inductor"))
    )
  )
  (nets
    (net (code "1") (name "/485A") (class "Default")
      (node (ref "J5") (pin "3") (pinfunction "3_3") (pintype "passive"))
      (node (ref "R17") (pin "1") (pinfunction "1_1") (pintype "passive"))
    )
    (net (code "2") (name "/485B") (class "Default")
      (node (ref "J5") (pin "2") (pinfunction "2_2") (pintype "passive"))
      (node (ref "R40") (pin "1") (pinfunction "1_1") (pintype "passive"))
    )
    (net (code "3") (name "/AVCC") (class "Default")
      (node (ref "C38") (pin "1") (pinfunction "1_1") (pintype "passive"))
      (node (ref "C39") (pin "1") (pinfunction "1_1") (pintype "passive"))
      (node (ref "C6") (pin "1") (pinfunction "1_1") (pintype "passive"))
      (node (ref "U1") (pin "13") (pinfunction "AVCC/VREFH_13") (pintype "power_in"))
      (node (ref "U1") (pin "19") (pinfunction "AVCC_19") (pintype "power_in"))
      (node (ref "Z1") (pin "1") (pinfunction "1_1") (pintype "passive"))
    )
    (net (code "4") (name "/AVSS") (class "Default")
      (node (ref "C38") (pin "2") (pinfunction "2_2") (pintype "passive"))
      (node (ref "C39") (pin "2") (pinfunction "2_2") (pintype "passive"))
      (node (ref "C6") (pin "2") (pinfunction "2_2") (pintype "passive"))
      (node (ref "U1") (pin "12") (pinfunction "AVSS/VREFL_12") (pintype "power_in"))
      (node (ref "U1") (pin "18") (pinfunction "AVSS_18") (pintype "power_in"))
      (node (ref "Z2") (pin "1") (pinfunction "1_1") (pintype "passive"))
    )
    (net (code "5") (name "/EARTH") (class "Default")
      (node (ref "J3") (pin "1") (pinfunction "1_1") (pintype "passive"))
      (node (ref "J5") (pin "1") (pinfunction "1_1") (pintype "passive"))
      (node (ref "T1") (pin "1") (pinfunction "PG_1") (pintype "passive"))
      (node (ref "T2") (pin "1") (pinfunction "PG_1") (pintype "passive"))
      (node (ref "T3") (pin "1") (pinfunction "PG_1") (pintype "passive"))
      (node (ref "T4") (pin "1") (pinfunction "PG_1") (pintype "passive"))
    )
    (net (code "6") (name "/HALL1") (class "Default")
      (node (ref "J8") (pin "2") (pinfunction "2_2") (pintype "passive"))
      (node (ref "Z11") (pin "1") (pinfunction "1_1") (pintype "passive"))
    )
    (net (code "7") (name "/HALL2") (class "Default")
      (node (ref "J8") (pin "3") (pinfunction "3_3") (pintype "passive"))
      (node (ref "Z12") (pin "1") (pinfunction "1_1") (pintype "passive"))
    )
    (net (code "8") (name "/HALL3") (class "Default")
      (node (ref "J8") (pin "4") (pinfunction "4_4") (pintype "passive"))
      (node (ref "Z13") (pin "1") (pinfunction "1_1") (pintype "passive"))
    )
    (net (code "9") (name "/HALL4") (class "Default")
      (node (ref "J8") (pin "5") (pinfunction "5_5") (pintype "passive"))
      (node (ref "Z14") (pin "1") (pinfunction "1_1") (pintype "passive"))
    )
    (net (code "10") (name "/HALL5") (class "Default")
      (node (ref "J8") (pin "6") (pinfunction "6_6") (pintype "passive"))
      (node (ref "Z15") (pin "1") (pinfunction "1_1") (pintype "passive"))
    )
    (net (code "11") (name "/HALL6") (class "Default")
      (node (ref "J8") (pin "7") (pinfunction "7_7") (pintype "passive"))
      (node (ref "Z16") (pin "1") (pinfunction "1_1") (pintype "passive"))
    )
    (net (code "12") (name "/HALL7") (class "Default")
      (node (ref "J8") (pin "8") (pinfunction "8_8") (pintype "passive"))
      (node (ref "Z17") (pin "1") (pinfunction "1_1") (pintype "passive"))
    )
    (net (code "13") (name "/HALL8") (class "Default")
      (node (ref "J8") (pin "9") (pinfunction "9_9") (pintype "passive"))
      (node (ref "Z18") (pin "1") (pinfunction "1_1") (pintype "passive"))
    )
    (net (code "14") (name "/MD") (class "Default")
      (node (ref "J7") (pin "1") (pinfunction "1_1") (pintype "passive"))
      (node (ref "R6") (pin "1") (pinfunction "1_1") (pintype "passive"))
      (node (ref "U1") (pin "60") (pinfunction "PB11/MD_60") (pintype "passive"))
    )
    (net (code "15") (name "/NRST") (class "Default")
      (node (ref "C34") (pin "1") (pinfunction "1_1") (pintype "passive"))
      (node (ref "R2") (pin "1") (pinfunction "1_1") (pintype "passive"))
      (node (ref "R3") (pin "2") (pinfunction "2_2") (pintype "passive"))
      (node (ref "U1") (pin "7") (pinfunction "NRST_7") (pintype "passive"))
    )
    (net (code "16") (name "/PA0") (class "Default")
      (node (ref "R62") (pin "2") (pinfunction "2_2") (pintype "passive"))
      (node (ref "U1") (pin "14") (pinfunction "PA0/ADC1_IN0_14") (pintype "passive"))
      (node (ref "U11") (pin "7") (pinfunction "SCLK_7") (pintype "passive"))
    )
    (net (code "17") (name "/PA1") (class "Default")
      (node (ref "R63") (pin "2") (pinfunction "2_2") (pintype "passive"))
      (node (ref "U1") (pin "15") (pinfunction "PA1/ADC1_IN1_15") (pintype "passive"))
      (node (ref "U11") (pin "6") (pinfunction "I/O_6") (pintype "passive"))
    )
    (net (code "18") (name "/PA2") (class "Default")
      (node (ref "R65") (pin "2") (pinfunction "2_2") (pintype "passive"))
      (node (ref "U1") (pin "16") (pinfunction "PA2/ADC1_IN2_16") (pintype "passive"))
      (node (ref "U11") (pin "5") (pinfunction "RST_5") (pintype "passive"))
    )
    (net (code "19") (name "/PA3") (class "Default")
      (node (ref "U1") (pin "17") (pinfunction "PA3/ADC1_IN3_17") (pintype "passive"))
    )
    (net (code "20") (name "/PA8") (class "Default")
      (node (ref "U1") (pin "41") (pinfunction "PA8_41") (pintype "passive"))
    )
    (net (code "21") (name "/PA9") (class "Default")
      (node (ref "U1") (pin "42") (pinfunction "PA9/USBFS_VBUS_42") (pintype "passive"))
    )
    (net (code "22") (name "/PA10") (class "Default")
      (node (ref "U1") (pin "43") (pinfunction "PA10/USBFS_ID_43") (pintype "passive"))
    )
    (net (code "23") (name "/PA11") (class "Default")
      (node (ref "U1") (pin "44") (pinfunction "PA11/USBFS_DM_44") (pintype "passive"))
    )
    (net (code "24") (name "/PA12") (class "Default")
      (node (ref "U1") (pin "45") (pinfunction "PA12/USBFS_DP_45") (pintype "passive"))
    )
    (net (code "25") (name "/PA15") (class "Default")
      (node (ref "C20") (pin "2") (pinfunction "2_2") (pintype "passive"))
      (node (ref "R32") (pin "2") (pinfunction "2_2") (pintype "passive"))
      (node (ref "U1") (pin "50") (pinfunction "PA15/TDI_50") (pintype "passive"))
      (node (ref "U9") (pin "16") (pinfunction "OUT_16") (pintype "passive"))
    )
    (net (code "26") (name "/PB0") (class "Default")
      (node (ref "U1") (pin "26") (pinfunction "PB0/ADC12_IN8_26") (pintype "passive"))
    )
    (net (code "27") (name "/PB1") (class "Default")
      (node (ref "U1") (pin "27") (pinfunction "PB1/ADC12_IN9_27") (pintype "passive"))
    )
    (net (code "28") (name "/PB2") (class "Default")
      (node (ref "U1") (pin "28") (pinfunction "PB2/PVD2EXINP_28") (pintype "passive"))
    )
    (net (code "29") (name "/PB3") (class "Default")
      (node (ref "U1") (pin "55") (pinfunction "PB3/JTDO_TRACESWO_55") (pintype "passive"))
    )
    (net (code "30") (name "/PB4") (class "Default")
      (node (ref "C40") (pin "2") (pinfunction "2_2") (pintype "passive"))
      (node (ref "R54") (pin "2") (pinfunction "2_2") (pintype "passive"))
      (node (ref "U1") (pin "56") (pinfunction "PB4/nTRST_56") (pintype "passive"))
      (node (ref "U10") (pin "14") (pinfunction "OUT_14") (pintype "passive"))
    )
    (net (code "31") (name "/PB5") (class "Default")
      (node (ref "C51") (pin "2") (pinfunction "2_2") (pintype "passive"))
      (node (ref "R57") (pin "2") (pinfunction "2_2") (pintype "passive"))
      (node (ref "U1") (pin "57") (pinfunction "PB5_57") (pintype "passive"))
      (node (ref "U10") (pin "12") (pinfunction "OUT_12") (pintype "passive"))
    )
    (net (code "32") (name "/PB6") (class "Default")
      (node (ref "C53") (pin "2") (pinfunction "2_2") (pintype "passive"))
      (node (ref "R60") (pin "2") (pinfunction "2_2") (pintype "passive"))
      (node (ref "U1") (pin "58") (pinfunction "PB6_58") (pintype "passive"))
      (node (ref "U10") (pin "10") (pinfunction "OUT_10") (pintype "passive"))
    )
    (net (code "33") (name "/PB10") (class "Default")
      (node (ref "U1") (pin "29") (pinfunction "PB10_29") (pintype "passive"))
    )
    (net (code "34") (name "/PB12") (class "Default")
      (node (ref "U1") (pin "33") (pinfunction "PB12_33") (pintype "passive"))
    )
    (net (code "35") (name "/PB13") (class "Default")
      (node (ref "U1") (pin "34") (pinfunction "PB13_34") (pintype "passive"))
    )
    (net (code "36") (name "/PC3") (class "Default")
      (node (ref "U1") (pin "11") (pinfunction "PC3/ADC1_IN13_11") (pintype "passive"))
    )
    (net (code "37") (name "/PC10") (class "Default")
      (node (ref "C27") (pin "2") (pinfunction "2_2") (pintype "passive"))
      (node (ref "R38") (pin "2") (pinfunction "2_2") (pintype "passive"))
      (node (ref "U1") (pin "51") (pinfunction "PC10_51") (pintype "passive"))
      (node (ref "U9") (pin "14") (pinfunction "OUT_14") (pintype "passive"))
    )
    (net (code "38") (name "/PC11") (class "Default")
      (node (ref "C29") (pin "2") (pinfunction "2_2") (pintype "passive"))
      (node (ref "R45") (pin "2") (pinfunction "2_2") (pintype "passive"))
      (node (ref "U1") (pin "52") (pinfunction "PC11_52") (pintype "passive"))
      (node (ref "U9") (pin "12") (pinfunction "OUT_12") (pintype "passive"))
    )
    (net (code "39") (name "/PC12") (class "Default")
      (node (ref "C31") (pin "2") (pinfunction "2_2") (pintype "passive"))
      (node (ref "R48") (pin "2") (pinfunction "2_2") (pintype "passive"))
      (node (ref "U1") (pin "53") (pinfunction "PC12_53") (pintype "passive"))
      (node (ref "U9") (pin "10") (pinfunction "OUT_10") (pintype "passive"))
    )
    (net (code "40") (name "/PD2") (class "Default")
      (node (ref "C35") (pin "2") (pinfunction "2_2") (pintype "passive"))
      (node (ref "R51") (pin "2") (pinfunction "2_2") (pintype "passive"))
      (node (ref "U1") (pin "54") (pinfunction "PD2_54") (pintype "passive"))
      (node (ref "U10") (pin "16") (pinfunction "OUT_16") (pintype "passive"))
    )
    (net (code "41") (name "/PH0") (class "Default")
      (node (ref "C37") (pin "2") (pinfunction "2_2") (pintype "passive"))
      (node (ref "U1") (pin "5") (pinfunction "PH0/XTAL_IN_5") (pintype "passive"))
      (node (ref "X1") (pin "2") (pinfunction "2_2") (pintype "passive"))
    )
    (net (code "42") (name "/PH1") (class "Default")
      (node (ref "C5") (pin "2") (pinfunction "2_2") (pintype "passive"))
      (node (ref "U1") (pin "6") (pinfunction "PH1/XTAL_OUT_6") (pintype "passive"))
      (node (ref "X1") (pin "1") (pinfunction "1_1") (pintype "passive"))
    )
    (net (code "43") (name "/RS485_A") (class "Default")
      (node (ref "J3") (pin "2") (pinfunction "2_2") (pintype "passive"))
      (node (ref "R15") (pin "1") (pinfunction "1_1") (pintype "passive"))
    )
    (net (code "44") (name "/RS485_B") (class "Default")
      (node (ref "J3") (pin "3") (pinfunction "3_3") (pintype "passive"))
      (node (ref "R21") (pin "1") (pinfunction "1_1") (pintype "passive"))
    )
    (net (code "45") (name "/RST") (class "Default")
      (node (ref "J2") (pin "1") (pinfunction "1_1") (pintype "passive"))
      (node (ref "R3") (pin "1") (pinfunction "1_1") (pintype "passive"))
    )
    (net (code "46") (name "/SWCLK") (class "Default")
      (node (ref "J2") (pin "2") (pinfunction "2_2") (pintype "passive"))
      (node (ref "R4") (pin "2") (pinfunction "2_2") (pintype "passive"))
      (node (ref "U1") (pin "49") (pinfunction "PA14/TCK_SWCLK_49") (pintype "passive"))
    )
    (net (code "47") (name "/SWDIO") (class "Default")
      (node (ref "J2") (pin "3") (pinfunction "3_3") (pintype "passive"))
      (node (ref "R5") (pin "2") (pinfunction "2_2") (pintype "passive"))
      (node (ref "U1") (pin "46") (pinfunction "PA13/TMS_SWDIO_46") (pintype "passive"))
    )
    (net (code "48") (name "/VCAP1") (class "Default")
      (node (ref "C48") (pin "1") (pinfunction "1_1") (pintype "passive"))
      (node (ref "U1") (pin "30") (pinfunction "VCAP__1_30") (pintype "power_in"))
    )
    (net (code "49") (name "/relay") (class "Default")
      (node (ref "C23") (pin "1") (pinfunction "1_1") (pintype "passive"))
      (node (ref "R43") (pin "1") (pinfunction "1_1") (pintype "passive"))
      (node (ref "U13") (pin "1") (pinfunction "IN1_1") (pintype "input"))
      (node (ref "U7") (pin "6") (pinfunction "3Y_6") (pintype "passive"))
    )
    (net (code "50") (name "3.3V") (class "Default")
      (node (ref "C1") (pin "1") (pinfunction "1_1") (pintype "passive"))
      (node (ref "C18") (pin "1") (pinfunction "1_1") (pintype "passive"))
      (node (ref "C19") (pin "1") (pinfunction "1_1") (pintype "passive"))
      (node (ref "C2") (pin "1") (pinfunction "1_1") (pintype "passive"))
      (node (ref "C21") (pin "1") (pinfunction "1_1") (pintype "passive"))
      (node (ref "C33") (pin "1") (pinfunction "1_1") (pintype "passive"))
      (node (ref "C42") (pin "1") (pinfunction "1_1") (pintype "passive"))
      (node (ref "C43") (pin "1") (pinfunction "1_1") (pintype "passive"))
      (node (ref "C44") (pin "1") (pinfunction "1_1") (pintype "passive"))
      (node (ref "C45") (pin "1") (pinfunction "1_1") (pintype "passive"))
      (node (ref "C46") (pin "1") (pinfunction "1_1") (pintype "passive"))
      (node (ref "C47") (pin "1") (pinfunction "1_1") (pintype "passive"))
      (node (ref "C56") (pin "1") (pinfunction "1_1") (pintype "passive"))
      (node (ref "C57") (pin "1") (pinfunction "1_1") (pintype "passive"))
      (node (ref "C58") (pin "1") (pinfunction "1_1") (pintype "passive"))
      (node (ref "C60") (pin "1") (pinfunction "1_1") (pintype "passive"))
      (node (ref "C68") (pin "1") (pinfunction "1_1") (pintype "passive"))
      (node (ref "C69") (pin "2") (pinfunction "2_2") (pintype "passive"))
      (node (ref "C7") (pin "1") (pinfunction "1_1") (pintype "passive"))
      (node (ref "C71") (pin "1") (pinfunction "1_1") (pintype "passive"))
      (node (ref "C72") (pin "1") (pinfunction "1_1") (pintype "passive"))
      (node (ref "C73") (pin "2") (pinfunction "2_2") (pintype "passive"))
      (node (ref "C74") (pin "1") (pinfunction "1_1") (pintype "passive"))
      (node (ref "C75") (pin "1") (pinfunction "1_1") (pintype "passive"))
      (node (ref "C76") (pin "2") (pinfunction "2_2") (pintype "passive"))
      (node (ref "C77") (pin "2") (pinfunction "2_2") (pintype "passive"))
      (node (ref "C78") (pin "2") (pinfunction "2_2") (pintype "passive"))
      (node (ref "C8") (pin "1") (pinfunction "1_1") (pintype "passive"))
      (node (ref "C80") (pin "1") (pinfunction "1_1") (pintype "passive"))
      (node (ref "C81") (pin "1") (pinfunction "1_1") (pintype "passive"))
      (node (ref "C82") (pin "1") (pinfunction "1_1") (pintype "passive"))
      (node (ref "C83") (pin "1") (pinfunction "1_1") (pintype "passive"))
      (node (ref "C84") (pin "1") (pinfunction "1_1") (pintype "passive"))
      (node (ref "C85") (pin "1") (pinfunction "1_1") (pintype "passive"))
      (node (ref "J2") (pin "5") (pinfunction "5_5") (pintype "passive"))
      (node (ref "R1") (pin "2") (pinfunction "2_2") (pintype "passive"))
      (node (ref "R11") (pin "2") (pinfunction "2_2") (pintype "passive"))
      (node (ref "R12") (pin "2") (pinfunction "2_2") (pintype "passive"))
      (node (ref "R13") (pin "1") (pinfunction "1_1") (pintype "passive"))
      (node (ref "R14") (pin "1") (pinfunction "1_1") (pintype "passive"))
      (node (ref "R16") (pin "1") (pinfunction "1_1") (pintype "passive"))
      (node (ref "R18") (pin "1") (pinfunction "1_1") (pintype "passive"))
      (node (ref "R19") (pin "1") (pinfunction "1_1") (pintype "passive"))
      (node (ref "R2") (pin "2") (pinfunction "2_2") (pintype "passive"))
      (node (ref "R23") (pin "1") (pinfunction "1_1") (pintype "passive"))
      (node (ref "R24") (pin "1") (pinfunction "1_1") (pintype "passive"))
      (node (ref "R32") (pin "1") (pinfunction "1_1") (pintype "passive"))
      (node (ref "R34") (pin "1") (pinfunction "1_1") (pintype "passive"))
      (node (ref "R35") (pin "1") (pinfunction "1_1") (pintype "passive"))
      (node (ref "R36") (pin "1") (pinfunction "1_1") (pintype "passive"))
      (node (ref "R38") (pin "1") (pinfunction "1_1") (pintype "passive"))
      (node (ref "R4") (pin "1") (pinfunction "1_1") (pintype "passive"))
      (node (ref "R42") (pin "1") (pinfunction "1_1") (pintype "passive"))
      (node (ref "R45") (pin "1") (pinfunction "1_1") (pintype "passive"))
      (node (ref "R48") (pin "1") (pinfunction "1_1") (pintype "passive"))
      (node (ref "R5") (pin "1") (pinfunction "1_1") (pintype "passive"))
      (node (ref "R51") (pin "1") (pinfunction "1_1") (pintype "passive"))
      (node (ref "R54") (pin "1") (pinfunction "1_1") (pintype "passive"))
      (node (ref "R57") (pin "1") (pinfunction "1_1") (pintype "passive"))
      (node (ref "R6") (pin "2") (pinfunction "2_2") (pintype "passive"))
      (node (ref "R60") (pin "1") (pinfunction "1_1") (pintype "passive"))
      (node (ref "R62") (pin "1") (pinfunction "1_1") (pintype "passive"))
      (node (ref "R63") (pin "1") (pinfunction "1_1") (pintype "passive"))
      (node (ref "R64") (pin "2") (pinfunction "2_2") (pintype "passive"))
      (node (ref "R65") (pin "1") (pinfunction "1_1") (pintype "passive"))
      (node (ref "R66") (pin "1") (pinfunction "1_1") (pintype "passive"))
      (node (ref "R67") (pin "1") (pinfunction "1_1") (pintype "passive"))
      (node (ref "R68") (pin "1") (pinfunction "1_1") (pintype "passive"))
      (node (ref "R69") (pin "1") (pinfunction "1_1") (pintype "passive"))
      (node (ref "R7") (pin "1") (pinfunction "1_1") (pintype "passive"))
      (node (ref "R70") (pin "1") (pinfunction "1_1") (pintype "passive"))
      (node (ref "R8") (pin "1") (pinfunction "1_1") (pintype "passive"))
      (node (ref "R9") (pin "1") (pinfunction "1_1") (pintype "passive"))
      (node (ref "U1") (pin "32") (pinfunction "VCC_32") (pintype "power_in"))
      (node (ref "U1") (pin "48") (pinfunction "VCC_48") (pintype "power_in"))
      (node (ref "U1") (pin "64") (pinfunction "VCC_64") (pintype "power_in"))
      (node (ref "U11") (pin "1") (pinfunction "VCC2_1") (pintype "passive"))
      (node (ref "U12") (pin "8") (pinfunction "VCC_8") (pintype "power_in"))
      (node (ref "U14") (pin "6") (pinfunction "VCC_6") (pintype "passive"))
      (node (ref "U2") (pin "2") (pinfunction "OUT_2") (pintype "passive"))
      (node (ref "U2") (pin "4") (pinfunction "OUT_4") (pintype "passive"))
      (node (ref "U4") (pin "8") (pinfunction "VCC_8") (pintype "power_in"))
      (node (ref "Z1") (pin "2") (pinfunction "2_2") (pintype "passive"))
    )
    (net (code "51") (name "3.3Vu") (class "Default")
      (node (ref "C10") (pin "1") (pinfunction "1_1") (pintype "passive"))
      (node (ref "C11") (pin "1") (pinfunction "1_1") (pintype "passive"))
      (node (ref "C13") (pin "1") (pinfunction "1_1") (pintype "passive"))
      (node (ref "C16") (pin "1") (pinfunction "1_1") (pintype "passive"))
      (node (ref "C49") (pin "1") (pinfunction "1_1") (pintype "passive"))
      (node (ref "C50") (pin "1") (pinfunction "1_1") (pintype "passive"))
      (node (ref "C59") (pin "1") (pinfunction "1_1") (pintype "passive"))
      (node (ref "C65") (pin "1") (pinfunction "1_1") (pintype "passive"))
      (node (ref "C66") (pin "1") (pinfunction "1_1") (pintype "passive"))
      (node (ref "C67") (pin "1") (pinfunction "1_1") (pintype "passive"))
      (node (ref "R25") (pin "2") (pinfunction "2_2") (pintype "passive"))
      (node (ref "R26") (pin "2") (pinfunction "2_2") (pintype "passive"))
      (node (ref "R27") (pin "2") (pinfunction "2_2") (pintype "passive"))
      (node (ref "R28") (pin "2") (pinfunction "2_2") (pintype "passive"))
      (node (ref "U5") (pin "14") (pinfunction "VCC_14") (pintype "passive"))
      (node (ref "U6") (pin "6") (pinfunction "VCC_6") (pintype "passive"))
      (node (ref "U7") (pin "14") (pinfunction "VCC_14") (pintype "passive"))
      (node (ref "U8") (pin "2") (pinfunction "OUT_2") (pintype "passive"))
      (node (ref "U8") (pin "4") (pinfunction "OUT_4") (pintype "passive"))
    )
    (net (code "52") (name "5V") (class "Default")
      (node (ref "U2") (pin "3") (pinfunction "IN_3") (pintype "passive"))
      (node (ref "Z3") (pin "2") (pinfunction "2_2") (pintype "passive"))
    )
    (net (code "53") (name "5Va") (class "Default")
      (node (ref "C14") (pin "1") (pinfunction "1_1") (pintype "passive"))
      (node (ref "C3") (pin "1") (pinfunction "1_1") (pintype "passive"))
      (node (ref "C4") (pin "1") (pinfunction "1_1") (pintype "passive"))
      (node (ref "C61") (pin "1") (pinfunction "1_1") (pintype "passive"))
      (node (ref "C62") (pin "1") (pinfunction "1_1") (pintype "passive"))
      (node (ref "C63") (pin "1") (pinfunction "1_1") (pintype "passive"))
      (node (ref "C64") (pin "1") (pinfunction "1_1") (pintype "passive"))
      (node (ref "C86") (pin "2") (pinfunction "2_2") (pintype "passive"))
      (node (ref "C87") (pin "2") (pinfunction "2_2") (pintype "passive"))
      (node (ref "U3") (pin "3") (pinfunction "+Vo_3") (pintype "passive"))
      (node (ref "Z3") (pin "1") (pinfunction "1_1") (pintype "passive"))
      (node (ref "Z6") (pin "1") (pinfunction "1_1") (pintype "passive"))
      (node (ref "Z9") (pin "1") (pinfunction "1_1") (pintype "passive"))
    )
    (net (code "54") (name "5Vf") (class "Default")
      (node (ref "C25") (pin "1") (pinfunction "1_1") (pintype "passive"))
      (node (ref "C26") (pin "1") (pinfunction "1_1") (pintype "passive"))
      (node (ref "Q1") (pin "1") (pinfunction "1_1") (pintype "passive"))
      (node (ref "U13") (pin "9") (pinfunction "COM_9") (pintype "passive"))
      (node (ref "Z9") (pin "2") (pinfunction "2_2") (pintype "passive"))
    )
    (net (code "55") (name "5Vu") (class "Default")
      (node (ref "C12") (pin "1") (pinfunction "1_1") (pintype "passive"))
      (node (ref "C9") (pin "1") (pinfunction "1_1") (pintype "passive"))
      (node (ref "U8") (pin "3") (pinfunction "IN_3") (pintype "passive"))
      (node (ref "Z6") (pin "2") (pinfunction "2_2") (pintype "passive"))
    )
    (net (code "56") (name "24V") (class "Default")
      (node (ref "C15") (pin "1") (pinfunction "1_1") (pintype "passive"))
      (node (ref "C24") (pin "1") (pinfunction "1_1") (pintype "passive"))
      (node (ref "D4") (pin "2") (pinfunction "K_2") (pintype "passive"))
      (node (ref "U3") (pin "2") (pinfunction "+VI_2") (pintype "passive"))
    )
    (net (code "57") (name "GND") (class "Default")
      (node (ref "BAT1") (pin "2") (pinfunction "GND_2") (pintype "passive"))
      (node (ref "C1") (pin "2") (pinfunction "2_2") (pintype "passive"))
      (node (ref "C18") (pin "2") (pinfunction "2_2") (pintype "passive"))
      (node (ref "C19") (pin "2") (pinfunction "2_2") (pintype "passive"))
      (node (ref "C2") (pin "2") (pinfunction "2_2") (pintype "passive"))
      (node (ref "C20") (pin "1") (pinfunction "1_1") (pintype "passive"))
      (node (ref "C21") (pin "2") (pinfunction "2_2") (pintype "passive"))
      (node (ref "C27") (pin "1") (pinfunction "1_1") (pintype "passive"))
      (node (ref "C29") (pin "1") (pinfunction "1_1") (pintype "passive"))
      (node (ref "C31") (pin "1") (pinfunction "1_1") (pintype "passive"))
      (node (ref "C33") (pin "2") (pinfunction "2_2") (pintype "passive"))
      (node (ref "C34") (pin "2") (pinfunction "2_2") (pintype "passive"))
      (node (ref "C35") (pin "1") (pinfunction "1_1") (pintype "passive"))
      (node (ref "C37") (pin "1") (pinfunction "1_1") (pintype "passive"))
      (node (ref "C40") (pin "1") (pinfunction "1_1") (pintype "passive"))
      (node (ref "C42") (pin "2") (pinfunction "2_2") (pintype "passive"))
      (node (ref "C43") (pin "2") (pinfunction "2_2") (pintype "passive"))
      (node (ref "C44") (pin "2") (pinfunction "2_2") (pintype "passive"))
      (node (ref "C45") (pin "2") (pinfunction "2_2") (pintype "passive"))
      (node (ref "C46") (pin "2") (pinfunction "2_2") (pintype "passive"))
      (node (ref "C47") (pin "2") (pinfunction "2_2") (pintype "passive"))
      (node (ref "C48") (pin "2") (pinfunction "2_2") (pintype "passive"))
      (node (ref "C5") (pin "1") (pinfunction "1_1") (pintype "passive"))
      (node (ref "C51") (pin "1") (pinfunction "1_1") (pintype "passive"))
      (node (ref "C53") (pin "1") (pinfunction "1_1") (pintype "passive"))
      (node (ref "C54") (pin "2") (pinfunction "2_2") (pintype "passive"))
      (node (ref "C55") (pin "2") (pinfunction "2_2") (pintype "passive"))
      (node (ref "C56") (pin "2") (pinfunction "2_2") (pintype "passive"))
      (node (ref "C57") (pin "2") (pinfunction "2_2") (pintype "passive"))
      (node (ref "C58") (pin "2") (pinfunction "2_2") (pintype "passive"))
      (node (ref "C60") (pin "2") (pinfunction "2_2") (pintype "passive"))
      (node (ref "C68") (pin "2") (pinfunction "2_2") (pintype "passive"))
      (node (ref "C69") (pin "1") (pinfunction "1_1") (pintype "passive"))
      (node (ref "C7") (pin "2") (pinfunction "2_2") (pintype "passive"))
      (node (ref "C71") (pin "2") (pinfunction "2_2") (pintype "passive"))
      (node (ref "C72") (pin "2") (pinfunction "2_2") (pintype "passive"))
      (node (ref "C73") (pin "1") (pinfunction "1_1") (pintype "passive"))
      (node (ref "C74") (pin "2") (pinfunction "2_2") (pintype "passive"))
      (node (ref "C75") (pin "2") (pinfunction "2_2") (pintype "passive"))
      (node (ref "C76") (pin "1") (pinfunction "1_1") (pintype "passive"))
      (node (ref "C77") (pin "1") (pinfunction "1_1") (pintype "passive"))
      (node (ref "C78") (pin "1") (pinfunction "1_1") (pintype "passive"))
      (node (ref "C8") (pin "2") (pinfunction "2_2") (pintype "passive"))
      (node (ref "C80") (pin "2") (pinfunction "2_2") (pintype "passive"))
      (node (ref "C81") (pin "2") (pinfunction "2_2") (pintype "passive"))
      (node (ref "C82") (pin "2") (pinfunction "2_2") (pintype "passive"))
      (node (ref "C83") (pin "2") (pinfunction "2_2") (pintype "passive"))
      (node (ref "C84") (pin "2") (pinfunction "2_2") (pintype "passive"))
      (node (ref "C85") (pin "2") (pinfunction "2_2") (pintype "passive"))
      (node (ref "J2") (pin "4") (pinfunction "4_4") (pintype "passive"))
      (node (ref "J7") (pin "2") (pinfunction "2_2") (pintype "passive"))
      (node (ref "LED5") (pin "2") (pinfunction "K_2") (pintype "passive"))
      (node (ref "R10") (pin "2") (pinfunction "2_2") (pintype "passive"))
      (node (ref "R41") (pin "2") (pinfunction "2_2") (pintype "passive"))
      (node (ref "U1") (pin "31") (pinfunction "VSS_31") (pintype "power_in"))
      (node (ref "U1") (pin "47") (pinfunction "VSS_47") (pintype "power_in"))
      (node (ref "U1") (pin "63") (pinfunction "VSS_63") (pintype "power_in"))
      (node (ref "U10") (pin "11") (pinfunction "GND_11") (pintype "passive"))
      (node (ref "U10") (pin "13") (pinfunction "GND_13") (pintype "passive"))
      (node (ref "U10") (pin "15") (pinfunction "GND_15") (pintype "passive"))
      (node (ref "U10") (pin "9") (pinfunction "GND_9") (pintype "passive"))
      (node (ref "U11") (pin "4") (pinfunction "GND_4") (pintype "passive"))
      (node (ref "U12") (pin "5") (pinfunction "GND_5") (pintype "power_in"))
      (node (ref "U14") (pin "7") (pinfunction "GND_7") (pintype "passive"))
      (node (ref "U2") (pin "1") (pinfunction "GND_1") (pintype "passive"))
      (node (ref "U4") (pin "5") (pinfunction "GND_5") (pintype "power_in"))
      (node (ref "U9") (pin "11") (pinfunction "GND_11") (pintype "passive"))
      (node (ref "U9") (pin "13") (pinfunction "GND_13") (pintype "passive"))
      (node (ref "U9") (pin "15") (pinfunction "GND_15") (pintype "passive"))
      (node (ref "U9") (pin "9") (pinfunction "GND_9") (pintype "passive"))
      (node (ref "Z2") (pin "2") (pinfunction "2_2") (pintype "passive"))
      (node (ref "Z4") (pin "2") (pinfunction "2_2") (pintype "passive"))
      (node (ref "Z8") (pin "1") (pinfunction "1_1") (pintype "passive"))
    )
    (net (code "58") (name "GND_24V") (class "Default")
      (node (ref "C15") (pin "2") (pinfunction "2_2") (pintype "passive"))
      (node (ref "C24") (pin "2") (pinfunction "2_2") (pintype "passive"))
      (node (ref "J1") (pin "1") (pinfunction "1_1") (pintype "passive"))
      (node (ref "U3") (pin "1") (pinfunction "-VI_1") (pintype "passive"))
    )
    (net (code "59") (name "GNDa") (class "Default")
      (node (ref "C14") (pin "2") (pinfunction "2_2") (pintype "passive"))
      (node (ref "C3") (pin "2") (pinfunction "2_2") (pintype "passive"))
      (node (ref "C4") (pin "2") (pinfunction "2_2") (pintype "passive"))
      (node (ref "C61") (pin "2") (pinfunction "2_2") (pintype "passive"))
      (node (ref "C62") (pin "2") (pinfunction "2_2") (pintype "passive"))
      (node (ref "C63") (pin "2") (pinfunction "2_2") (pintype "passive"))
      (node (ref "C64") (pin "2") (pinfunction "2_2") (pintype "passive"))
      (node (ref "C86") (pin "1") (pinfunction "1_1") (pintype "passive"))
      (node (ref "C87") (pin "1") (pinfunction "1_1") (pintype "passive"))
      (node (ref "U3") (pin "5") (pinfunction "-Vo_5") (pintype "passive"))
      (node (ref "Z10") (pin "1") (pinfunction "1_1") (pintype "passive"))
      (node (ref "Z4") (pin "1") (pinfunction "1_1") (pintype "passive"))
      (node (ref "Z7") (pin "1") (pinfunction "1_1") (pintype "passive"))
    )
    (net (code "60") (name "GNDf") (class "Default")
      (node (ref "C23") (pin "2") (pinfunction "2_2") (pintype "passive"))
      (node (ref "C25") (pin "2") (pinfunction "2_2") (pintype "passive"))
      (node (ref "C26") (pin "2") (pinfunction "2_2") (pintype "passive"))
      (node (ref "R43") (pin "2") (pinfunction "2_2") (pintype "passive"))
      (node (ref "U13") (pin "2") (pinfunction "IN2_2") (pintype "input"))
      (node (ref "U13") (pin "3") (pinfunction "IN3_3") (pintype "input"))
      (node (ref "U13") (pin "4") (pinfunction "IN4_4") (pintype "input"))
      (node (ref "U13") (pin "5") (pinfunction "IN5_5") (pintype "input"))
      (node (ref "U13") (pin "6") (pinfunction "IN6_6") (pintype "input"))
      (node (ref "U13") (pin "7") (pinfunction "IN7_7") (pintype "input"))
      (node (ref "U13") (pin "8") (pinfunction "GND_8") (pintype "passive"))
      (node (ref "Z10") (pin "2") (pinfunction "2_2") (pintype "passive"))
      (node (ref "Z5") (pin "2") (pinfunction "2_2") (pintype "passive"))
    )
    (net (code "61") (name "GNDu") (class "Default")
      (node (ref "C10") (pin "2") (pinfunction "2_2") (pintype "passive"))
      (node (ref "C11") (pin "2") (pinfunction "2_2") (pintype "passive"))
      (node (ref "C12") (pin "2") (pinfunction "2_2") (pintype "passive"))
      (node (ref "C13") (pin "2") (pinfunction "2_2") (pintype "passive"))
      (node (ref "C16") (pin "2") (pinfunction "2_2") (pintype "passive"))
      (node (ref "C49") (pin "2") (pinfunction "2_2") (pintype "passive"))
      (node (ref "C50") (pin "2") (pinfunction "2_2") (pintype "passive"))
      (node (ref "C59") (pin "2") (pinfunction "2_2") (pintype "passive"))
      (node (ref "C65") (pin "2") (pinfunction "2_2") (pintype "passive"))
      (node (ref "C66") (pin "2") (pinfunction "2_2") (pintype "passive"))
      (node (ref "C67") (pin "2") (pinfunction "2_2") (pintype "passive"))
      (node (ref "C9") (pin "2") (pinfunction "2_2") (pintype "passive"))
      (node (ref "U5") (pin "7") (pinfunction "GND_7") (pintype "passive"))
      (node (ref "U6") (pin "7") (pinfunction "GND_7") (pintype "passive"))
      (node (ref "U7") (pin "7") (pinfunction "GND_7") (pintype "passive"))
      (node (ref "U7") (pin "9") (pinfunction "4A_9") (pintype "passive"))
      (node (ref "U8") (pin "1") (pinfunction "GND_1") (pintype "passive"))
      (node (ref "Z5") (pin "1") (pinfunction "1_1") (pintype "passive"))
      (node (ref "Z7") (pin "2") (pinfunction "2_2") (pintype "passive"))
      (node (ref "Z8") (pin "2") (pinfunction "2_2") (pintype "passive"))
    )
    (net (code "62") (name "INCOM1") (class "Default")
      (node (ref "J8") (pin "1") (pinfunction "1_1") (pintype "passive"))
      (node (ref "R30") (pin "2") (pinfunction "2_2") (pintype "passive"))
      (node (ref "R37") (pin "2") (pinfunction "2_2") (pintype "passive"))
      (node (ref "R44") (pin "2") (pinfunction "2_2") (pintype "passive"))
      (node (ref "R47") (pin "2") (pinfunction "2_2") (pintype "passive"))
      (node (ref "R50") (pin "2") (pinfunction "2_2") (pintype "passive"))
      (node (ref "R53") (pin "2") (pinfunction "2_2") (pintype "passive"))
      (node (ref "R56") (pin "2") (pinfunction "2_2") (pintype "passive"))
      (node (ref "R59") (pin "2") (pinfunction "2_2") (pintype "passive"))
    )
    (net (code "63") (name "Net-(C17-Pad1)") (class "Default")
      (node (ref "C17") (pin "1") (pinfunction "1_1") (pintype "passive"))
      (node (ref "R30") (pin "1") (pinfunction "1_1") (pintype "passive"))
      (node (ref "U9") (pin "1") (pinfunction "A_1") (pintype "passive"))
    )
    (net (code "64") (name "Net-(C17-Pad2)") (class "Default")
      (node (ref "C17") (pin "2") (pinfunction "2_2") (pintype "passive"))
      (node (ref "R33") (pin "1") (pinfunction "1_1") (pintype "passive"))
      (node (ref "U9") (pin "2") (pinfunction "K_2") (pintype "passive"))
    )
    (net (code "65") (name "Net-(C22-Pad1)") (class "Default")
      (node (ref "C22") (pin "1") (pinfunction "1_1") (pintype "passive"))
      (node (ref "R37") (pin "1") (pinfunction "1_1") (pintype "passive"))
      (node (ref "U9") (pin "3") (pinfunction "A_3") (pintype "passive"))
    )
    (net (code "66") (name "Net-(C22-Pad2)") (class "Default")
      (node (ref "C22") (pin "2") (pinfunction "2_2") (pintype "passive"))
      (node (ref "R39") (pin "1") (pinfunction "1_1") (pintype "passive"))
      (node (ref "U9") (pin "4") (pinfunction "K_4") (pintype "passive"))
    )
    (net (code "67") (name "Net-(C28-Pad1)") (class "Default")
      (node (ref "C28") (pin "1") (pinfunction "1_1") (pintype "passive"))
      (node (ref "R44") (pin "1") (pinfunction "1_1") (pintype "passive"))
      (node (ref "U9") (pin "5") (pinfunction "A_5") (pintype "passive"))
    )
    (net (code "68") (name "Net-(C28-Pad2)") (class "Default")
      (node (ref "C28") (pin "2") (pinfunction "2_2") (pintype "passive"))
      (node (ref "R46") (pin "1") (pinfunction "1_1") (pintype "passive"))
      (node (ref "U9") (pin "6") (pinfunction "K_6") (pintype "passive"))
    )
    (net (code "69") (name "Net-(C30-Pad1)") (class "Default")
      (node (ref "C30") (pin "1") (pinfunction "1_1") (pintype "passive"))
      (node (ref "R47") (pin "1") (pinfunction "1_1") (pintype "passive"))
      (node (ref "U9") (pin "7") (pinfunction "A_7") (pintype "passive"))
    )
    (net (code "70") (name "Net-(C30-Pad2)") (class "Default")
      (node (ref "C30") (pin "2") (pinfunction "2_2") (pintype "passive"))
      (node (ref "R49") (pin "1") (pinfunction "1_1") (pintype "passive"))
      (node (ref "U9") (pin "8") (pinfunction "K_8") (pintype "passive"))
    )
    (net (code "71") (name "Net-(C32-Pad1)") (class "Default")
      (node (ref "C32") (pin "1") (pinfunction "1_1") (pintype "passive"))
      (node (ref "R50") (pin "1") (pinfunction "1_1") (pintype "passive"))
      (node (ref "U10") (pin "1") (pinfunction "A_1") (pintype "passive"))
    )
    (net (code "72") (name "Net-(C32-Pad2)") (class "Default")
      (node (ref "C32") (pin "2") (pinfunction "2_2") (pintype "passive"))
      (node (ref "R52") (pin "1") (pinfunction "1_1") (pintype "passive"))
      (node (ref "U10") (pin "2") (pinfunction "K_2") (pintype "passive"))
    )
    (net (code "73") (name "Net-(C36-Pad1)") (class "Default")
      (node (ref "C36") (pin "1") (pinfunction "1_1") (pintype "passive"))
      (node (ref "R53") (pin "1") (pinfunction "1_1") (pintype "passive"))
      (node (ref "U10") (pin "3") (pinfunction "A_3") (pintype "passive"))
    )
    (net (code "74") (name "Net-(C36-Pad2)") (class "Default")
      (node (ref "C36") (pin "2") (pinfunction "2_2") (pintype "passive"))
      (node (ref "R55") (pin "1") (pinfunction "1_1") (pintype "passive"))
      (node (ref "U10") (pin "4") (pinfunction "K_4") (pintype "passive"))
    )
    (net (code "75") (name "Net-(C41-Pad1)") (class "Default")
      (node (ref "C41") (pin "1") (pinfunction "1_1") (pintype "passive"))
      (node (ref "R56") (pin "1") (pinfunction "1_1") (pintype "passive"))
      (node (ref "U10") (pin "5") (pinfunction "A_5") (pintype "passive"))
    )
    (net (code "76") (name "Net-(C41-Pad2)") (class "Default")
      (node (ref "C41") (pin "2") (pinfunction "2_2") (pintype "passive"))
      (node (ref "R58") (pin "1") (pinfunction "1_1") (pintype "passive"))
      (node (ref "U10") (pin "6") (pinfunction "K_6") (pintype "passive"))
    )
    (net (code "77") (name "Net-(C52-Pad1)") (class "Default")
      (node (ref "C52") (pin "1") (pinfunction "1_1") (pintype "passive"))
      (node (ref "R59") (pin "1") (pinfunction "1_1") (pintype "passive"))
      (node (ref "U10") (pin "7") (pinfunction "A_7") (pintype "passive"))
    )
    (net (code "78") (name "Net-(C52-Pad2)") (class "Default")
      (node (ref "C52") (pin "2") (pinfunction "2_2") (pintype "passive"))
      (node (ref "R61") (pin "1") (pinfunction "1_1") (pintype "passive"))
      (node (ref "U10") (pin "8") (pinfunction "K_8") (pintype "passive"))
    )
    (net (code "79") (name "Net-(D4-A)") (class "Default")
      (node (ref "D4") (pin "1") (pinfunction "A_1") (pintype "passive"))
      (node (ref "J1") (pin "2") (pinfunction "2_2") (pintype "passive"))
    )
    (net (code "80") (name "Net-(LED5-A)") (class "Default")
      (node (ref "LED5") (pin "1") (pinfunction "A_1") (pintype "passive"))
      (node (ref "R1") (pin "1") (pinfunction "1_1") (pintype "passive"))
    )
    (net (code "81") (name "Net-(PC4-A)") (class "Default")
      (node (ref "PC4") (pin "1") (pinfunction "A_1") (pintype "passive"))
      (node (ref "R11") (pin "1") (pinfunction "1_1") (pintype "passive"))
    )
    (net (code "82") (name "Net-(PC5-A)") (class "Default")
      (node (ref "PC5") (pin "1") (pinfunction "A_1") (pintype "passive"))
      (node (ref "R12") (pin "1") (pinfunction "1_1") (pintype "passive"))
    )
    (net (code "83") (name "Net-(R33-Pad2)") (class "Default")
      (node (ref "R33") (pin "2") (pinfunction "2_2") (pintype "passive"))
      (node (ref "Z11") (pin "2") (pinfunction "2_2") (pintype "passive"))
    )
    (net (code "84") (name "Net-(R39-Pad2)") (class "Default")
      (node (ref "R39") (pin "2") (pinfunction "2_2") (pintype "passive"))
      (node (ref "Z12") (pin "2") (pinfunction "2_2") (pintype "passive"))
    )
    (net (code "85") (name "Net-(R46-Pad2)") (class "Default")
      (node (ref "R46") (pin "2") (pinfunction "2_2") (pintype "passive"))
      (node (ref "Z13") (pin "2") (pinfunction "2_2") (pintype "passive"))
    )
    (net (code "86") (name "Net-(R49-Pad2)") (class "Default")
      (node (ref "R49") (pin "2") (pinfunction "2_2") (pintype "passive"))
      (node (ref "Z14") (pin "2") (pinfunction "2_2") (pintype "passive"))
    )
    (net (code "87") (name "Net-(R52-Pad2)") (class "Default")
      (node (ref "R52") (pin "2") (pinfunction "2_2") (pintype "passive"))
      (node (ref "Z15") (pin "2") (pinfunction "2_2") (pintype "passive"))
    )
    (net (code "88") (name "Net-(R55-Pad2)") (class "Default")
      (node (ref "R55") (pin "2") (pinfunction "2_2") (pintype "passive"))
      (node (ref "Z16") (pin "2") (pinfunction "2_2") (pintype "passive"))
    )
    (net (code "89") (name "Net-(R58-Pad2)") (class "Default")
      (node (ref "R58") (pin "2") (pinfunction "2_2") (pintype "passive"))
      (node (ref "Z17") (pin "2") (pinfunction "2_2") (pintype "passive"))
    )
    (net (code "90") (name "Net-(R61-Pad2)") (class "Default")
      (node (ref "R61") (pin "2") (pinfunction "2_2") (pintype "passive"))
      (node (ref "Z18") (pin "2") (pinfunction "2_2") (pintype "passive"))
    )
    (net (code "91") (name "Net-(U4-A)") (class "Default")
      (node (ref "R14") (pin "2") (pinfunction "2_2") (pintype "passive"))
      (node (ref "R15") (pin "2") (pinfunction "2_2") (pintype "passive"))
      (node (ref "R22") (pin "2") (pinfunction "2_2") (pintype "passive"))
      (node (ref "U4") (pin "6") (pinfunction "A_6") (pintype "passive"))
    )
    (net (code "92") (name "Net-(U4-B)") (class "Default")
      (node (ref "R10") (pin "1") (pinfunction "1_1") (pintype "passive"))
      (node (ref "R21") (pin "2") (pinfunction "2_2") (pintype "passive"))
      (node (ref "R22") (pin "1") (pinfunction "1_1") (pintype "passive"))
      (node (ref "U4") (pin "7") (pinfunction "B_7") (pintype "passive"))
    )
    (net (code "93") (name "Net-(U5-1A)") (class "Default")
      (node (ref "U5") (pin "1") (pinfunction "1A_1") (pintype "passive"))
      (node (ref "U5") (pin "12") (pinfunction "6Y_12") (pintype "passive"))
    )
    (net (code "94") (name "Net-(U5-1Y)") (class "Default")
      (node (ref "U5") (pin "2") (pinfunction "1Y_2") (pintype "passive"))
      (node (ref "U6") (pin "3") (pinfunction "RXD_3") (pintype "passive"))
    )
    (net (code "95") (name "Net-(U5-2A)") (class "Default")
      (node (ref "R25") (pin "1") (pinfunction "1_1") (pintype "passive"))
      (node (ref "U5") (pin "3") (pinfunction "2A_3") (pintype "passive"))
      (node (ref "U6") (pin "4") (pinfunction "TXD_4") (pintype "passive"))
    )
    (net (code "96") (name "Net-(U5-2Y)") (class "Default")
      (node (ref "U5") (pin "11") (pinfunction "5A_11") (pintype "passive"))
      (node (ref "U5") (pin "4") (pinfunction "2Y_4") (pintype "passive"))
    )
    (net (code "97") (name "Net-(U5-3A)") (class "Default")
      (node (ref "R26") (pin "1") (pinfunction "1_1") (pintype "passive"))
      (node (ref "R29") (pin "2") (pinfunction "2_2") (pintype "passive"))
      (node (ref "U5") (pin "5") (pinfunction "3A_5") (pintype "passive"))
    )
    (net (code "98") (name "Net-(U5-3Y)") (class "Default")
      (node (ref "U5") (pin "6") (pinfunction "3Y_6") (pintype "passive"))
      (node (ref "U5") (pin "9") (pinfunction "4A_9") (pintype "passive"))
    )
    (net (code "99") (name "Net-(U6-AUX)") (class "Default")
      (node (ref "R29") (pin "1") (pinfunction "1_1") (pintype "passive"))
      (node (ref "U6") (pin "5") (pinfunction "AUX_5") (pintype "passive"))
    )
    (net (code "100") (name "Net-(U6-M0)") (class "Default")
      (node (ref "R27") (pin "1") (pinfunction "1_1") (pintype "passive"))
      (node (ref "U6") (pin "1") (pinfunction "M0_1") (pintype "passive"))
      (node (ref "U7") (pin "10") (pinfunction "5Y_10") (pintype "passive"))
    )
    (net (code "101") (name "Net-(U6-M1)") (class "Default")
      (node (ref "R28") (pin "1") (pinfunction "1_1") (pintype "passive"))
      (node (ref "U6") (pin "2") (pinfunction "M1_2") (pintype "passive"))
      (node (ref "U7") (pin "12") (pinfunction "6Y_12") (pintype "passive"))
    )
    (net (code "102") (name "Net-(U7-1Y)") (class "Default")
      (node (ref "U7") (pin "13") (pinfunction "6A_13") (pintype "passive"))
      (node (ref "U7") (pin "2") (pinfunction "1Y_2") (pintype "passive"))
    )
    (net (code "103") (name "Net-(U7-2Y)") (class "Default")
      (node (ref "U7") (pin "11") (pinfunction "5A_11") (pintype "passive"))
      (node (ref "U7") (pin "4") (pinfunction "2Y_4") (pintype "passive"))
    )
    (net (code "104") (name "Net-(U11-X1)") (class "Default")
      (node (ref "U11") (pin "2") (pinfunction "X1_2") (pintype "passive"))
      (node (ref "X2") (pin "2") (pinfunction "2_2") (pintype "passive"))
    )
    (net (code "105") (name "Net-(U11-X2)") (class "Default")
      (node (ref "U11") (pin "3") (pinfunction "X2_3") (pintype "passive"))
      (node (ref "X2") (pin "1") (pinfunction "1_1") (pintype "passive"))
    )
    (net (code "106") (name "Net-(U12-A)") (class "Default")
      (node (ref "R16") (pin "2") (pinfunction "2_2") (pintype "passive"))
      (node (ref "R17") (pin "2") (pinfunction "2_2") (pintype "passive"))
      (node (ref "R31") (pin "2") (pinfunction "2_2") (pintype "passive"))
      (node (ref "U12") (pin "6") (pinfunction "A_6") (pintype "passive"))
    )
    (net (code "107") (name "Net-(U12-B)") (class "Default")
      (node (ref "R31") (pin "1") (pinfunction "1_1") (pintype "passive"))
      (node (ref "R40") (pin "2") (pinfunction "2_2") (pintype "passive"))
      (node (ref "R41") (pin "1") (pinfunction "1_1") (pintype "passive"))
      (node (ref "U12") (pin "7") (pinfunction "B_7") (pintype "passive"))
    )
    (net (code "108") (name "Net-(U13-OUT1)") (class "Default")
      (node (ref "Q1") (pin "16") (pinfunction "16_16") (pintype "passive"))
      (node (ref "U13") (pin "16") (pinfunction "OUT1_16") (pintype "passive"))
    )
    (net (code "109") (name "Net-(U14-~{RST})") (class "Default")
      (node (ref "R64") (pin "1") (pinfunction "1_1") (pintype "passive"))
      (node (ref "U14") (pin "3") (pinfunction "~{RST}_3") (pintype "passive"))
    )
    (net (code "110") (name "Net-(U14-~{WP})") (class "Default")
      (node (ref "R66") (pin "2") (pinfunction "2_2") (pintype "passive"))
      (node (ref "U14") (pin "5") (pinfunction "~{WP}_5") (pintype "passive"))
    )
    (net (code "111") (name "PA4") (class "Default")
      (node (ref "R67") (pin "2") (pinfunction "2_2") (pintype "passive"))
      (node (ref "U1") (pin "20") (pinfunction "PA4/ADC12_IN4_20") (pintype "passive"))
      (node (ref "U14") (pin "4") (pinfunction "~{CS}_4") (pintype "passive"))
    )
    (net (code "112") (name "PA5") (class "Default")
      (node (ref "R68") (pin "2") (pinfunction "2_2") (pintype "passive"))
      (node (ref "U1") (pin "21") (pinfunction "PA5/ADC12_IN5_21") (pintype "passive"))
      (node (ref "U14") (pin "2") (pinfunction "SCK_2") (pintype "passive"))
    )
    (net (code "113") (name "PA6") (class "Default")
      (node (ref "R69") (pin "2") (pinfunction "2_2") (pintype "passive"))
      (node (ref "U1") (pin "22") (pinfunction "PA6/ADC12_IN6_22") (pintype "passive"))
      (node (ref "U14") (pin "1") (pinfunction "SI_1") (pintype "passive"))
    )
    (net (code "114") (name "PA7") (class "Default")
      (node (ref "R70") (pin "2") (pinfunction "2_2") (pintype "passive"))
      (node (ref "U1") (pin "23") (pinfunction "PA7/ADC12_IN7_23") (pintype "passive"))
      (node (ref "U14") (pin "8") (pinfunction "SO_8") (pintype "passive"))
    )
    (net (code "115") (name "PB7") (class "Default")
      (node (ref "R36") (pin "2") (pinfunction "2_2") (pintype "passive"))
      (node (ref "U1") (pin "59") (pinfunction "PB7_59") (pintype "passive"))
      (node (ref "U4") (pin "4") (pinfunction "DI_4") (pintype "passive"))
    )
    (net (code "116") (name "PB8") (class "Default")
      (node (ref "R35") (pin "2") (pinfunction "2_2") (pintype "passive"))
      (node (ref "U1") (pin "61") (pinfunction "PB8_61") (pintype "passive"))
      (node (ref "U4") (pin "2") (pinfunction "/RE_2") (pintype "passive"))
      (node (ref "U4") (pin "3") (pinfunction "DE_3") (pintype "passive"))
    )
    (net (code "117") (name "PB9") (class "Default")
      (node (ref "R34") (pin "2") (pinfunction "2_2") (pintype "passive"))
      (node (ref "U1") (pin "62") (pinfunction "PB9_62") (pintype "passive"))
      (node (ref "U4") (pin "1") (pinfunction "RO_1") (pintype "passive"))
    )
    (net (code "118") (name "PB14") (class "Default")
      (node (ref "R24") (pin "2") (pinfunction "2_2") (pintype "passive"))
      (node (ref "U1") (pin "35") (pinfunction "PB14_35") (pintype "passive"))
      (node (ref "U7") (pin "5") (pinfunction "3A_5") (pintype "passive"))
    )
    (net (code "119") (name "PB15") (class "Default")
      (node (ref "R23") (pin "2") (pinfunction "2_2") (pintype "passive"))
      (node (ref "U1") (pin "36") (pinfunction "PB15_36") (pintype "passive"))
      (node (ref "U7") (pin "3") (pinfunction "2A_3") (pintype "passive"))
    )
    (net (code "120") (name "PC0") (class "Default")
      (node (ref "R7") (pin "2") (pinfunction "2_2") (pintype "passive"))
      (node (ref "U1") (pin "8") (pinfunction "PC0/ADC12_IN10_8") (pintype "passive"))
      (node (ref "U12") (pin "1") (pinfunction "RO_1") (pintype "passive"))
    )
    (net (code "121") (name "PC1") (class "Default")
      (node (ref "R8") (pin "2") (pinfunction "2_2") (pintype "passive"))
      (node (ref "U1") (pin "9") (pinfunction "PC1/ADC12_IN11_9") (pintype "passive"))
      (node (ref "U12") (pin "2") (pinfunction "/RE_2") (pintype "passive"))
      (node (ref "U12") (pin "3") (pinfunction "DE_3") (pintype "passive"))
    )
    (net (code "122") (name "PC2") (class "Default")
      (node (ref "R13") (pin "2") (pinfunction "2_2") (pintype "passive"))
      (node (ref "U1") (pin "10") (pinfunction "PC2/ADC1_IN12_10") (pintype "passive"))
      (node (ref "U12") (pin "4") (pinfunction "DI_4") (pintype "passive"))
    )
    (net (code "123") (name "PC4") (class "Default")
      (node (ref "PC4") (pin "2") (pinfunction "K_2") (pintype "passive"))
      (node (ref "U1") (pin "24") (pinfunction "PC4/ADC1_IN14_24") (pintype "passive"))
    )
    (net (code "124") (name "PC5") (class "Default")
      (node (ref "PC5") (pin "2") (pinfunction "K_2") (pintype "passive"))
      (node (ref "U1") (pin "25") (pinfunction "PC5/ADC1_IN15_25") (pintype "passive"))
    )
    (net (code "125") (name "PC6") (class "Default")
      (node (ref "R42") (pin "2") (pinfunction "2_2") (pintype "passive"))
      (node (ref "U1") (pin "37") (pinfunction "PC6_37") (pintype "passive"))
      (node (ref "U7") (pin "1") (pinfunction "1A_1") (pintype "passive"))
    )
    (net (code "126") (name "PC7") (class "Default")
      (node (ref "R19") (pin "2") (pinfunction "2_2") (pintype "passive"))
      (node (ref "U1") (pin "38") (pinfunction "PC7_38") (pintype "passive"))
      (node (ref "U5") (pin "13") (pinfunction "6A_13") (pintype "passive"))
    )
    (net (code "127") (name "PC8") (class "Default")
      (node (ref "R18") (pin "2") (pinfunction "2_2") (pintype "passive"))
      (node (ref "U1") (pin "39") (pinfunction "PC8_39") (pintype "passive"))
      (node (ref "U5") (pin "10") (pinfunction "5Y_10") (pintype "passive"))
    )
    (net (code "128") (name "PC9") (class "Default")
      (node (ref "R9") (pin "2") (pinfunction "2_2") (pintype "passive"))
      (node (ref "U1") (pin "40") (pinfunction "PC9_40") (pintype "passive"))
      (node (ref "U5") (pin "8") (pinfunction "4Y_8") (pintype "passive"))
    )
    (net (code "129") (name "R1-1") (class "Default")
      (node (ref "J6") (pin "1") (pinfunction "1_1") (pintype "passive"))
      (node (ref "Q1") (pin "12") (pinfunction "12_12") (pintype "passive"))
    )
    (net (code "130") (name "R1-2") (class "Default")
      (node (ref "J6") (pin "2") (pinfunction "2_2") (pintype "passive"))
      (node (ref "Q1") (pin "9") (pinfunction "9_9") (pintype "passive"))
    )
    (net (code "131") (name "R2-1") (class "Default")
      (node (ref "J6") (pin "4") (pinfunction "4_4") (pintype "passive"))
      (node (ref "Q1") (pin "5") (pinfunction "5_5") (pintype "passive"))
    )
    (net (code "132") (name "R2-2") (class "Default")
      (node (ref "J6") (pin "3") (pinfunction "3_3") (pintype "passive"))
      (node (ref "Q1") (pin "8") (pinfunction "8_8") (pintype "passive"))
    )
    (net (code "133") (name "VBAT") (class "Default")
      (node (ref "BAT1") (pin "1") (pinfunction "VCC_1") (pintype "passive"))
      (node (ref "C54") (pin "1") (pinfunction "1_1") (pintype "passive"))
      (node (ref "C55") (pin "1") (pinfunction "1_1") (pintype "passive"))
      (node (ref "U11") (pin "8") (pinfunction "VCC1_8") (pintype "passive"))
    )
    (net (code "134") (name "unconnected-(U1-PC13-Pad2)") (class "Default")
      (node (ref "U1") (pin "2") (pinfunction "PC13_2") (pintype "passive"))
    )
    (net (code "135") (name "unconnected-(U1-PC14{slash}XTAL32_OUT-Pad3)") (class "Default")
      (node (ref "U1") (pin "3") (pinfunction "PC14/XTAL32_OUT_3") (pintype "passive"))
    )
    (net (code "136") (name "unconnected-(U1-PC15{slash}XTAL32_IN-Pad4)") (class "Default")
      (node (ref "U1") (pin "4") (pinfunction "PC15/XTAL32_IN_4") (pintype "passive"))
    )
    (net (code "137") (name "unconnected-(U1-PH2-Pad1)") (class "Default")
      (node (ref "U1") (pin "1") (pinfunction "PH2_1") (pintype "passive"))
    )
    (net (code "138") (name "unconnected-(U7-4Y-Pad8)") (class "Default")
      (node (ref "U7") (pin "8") (pinfunction "4Y_8") (pintype "passive"))
    )
    (net (code "139") (name "unconnected-(U13-OUT2-Pad15)") (class "Default")
      (node (ref "U13") (pin "15") (pinfunction "OUT2_15") (pintype "passive"))
    )
    (net (code "140") (name "unconnected-(U13-OUT3-Pad14)") (class "Default")
      (node (ref "U13") (pin "14") (pinfunction "OUT3_14") (pintype "passive"))
    )
    (net (code "141") (name "unconnected-(U13-OUT4-Pad13)") (class "Default")
      (node (ref "U13") (pin "13") (pinfunction "OUT4_13") (pintype "passive"))
    )
    (net (code "142") (name "unconnected-(U13-OUT5-Pad12)") (class "Default")
      (node (ref "U13") (pin "12") (pinfunction "OUT5_12") (pintype "passive"))
    )
    (net (code "143") (name "unconnected-(U13-OUT6-Pad11)") (class "Default")
      (node (ref "U13") (pin "11") (pinfunction "OUT6_11") (pintype "passive"))
    )
    (net (code "144") (name "unconnected-(U13-OUT7-Pad10)") (class "Default")
      (node (ref "U13") (pin "10") (pinfunction "OUT7_10") (pintype "passive"))
    )
  )
)
